# V2.net
KiCad netlist of a schematic drawn in EAGLE
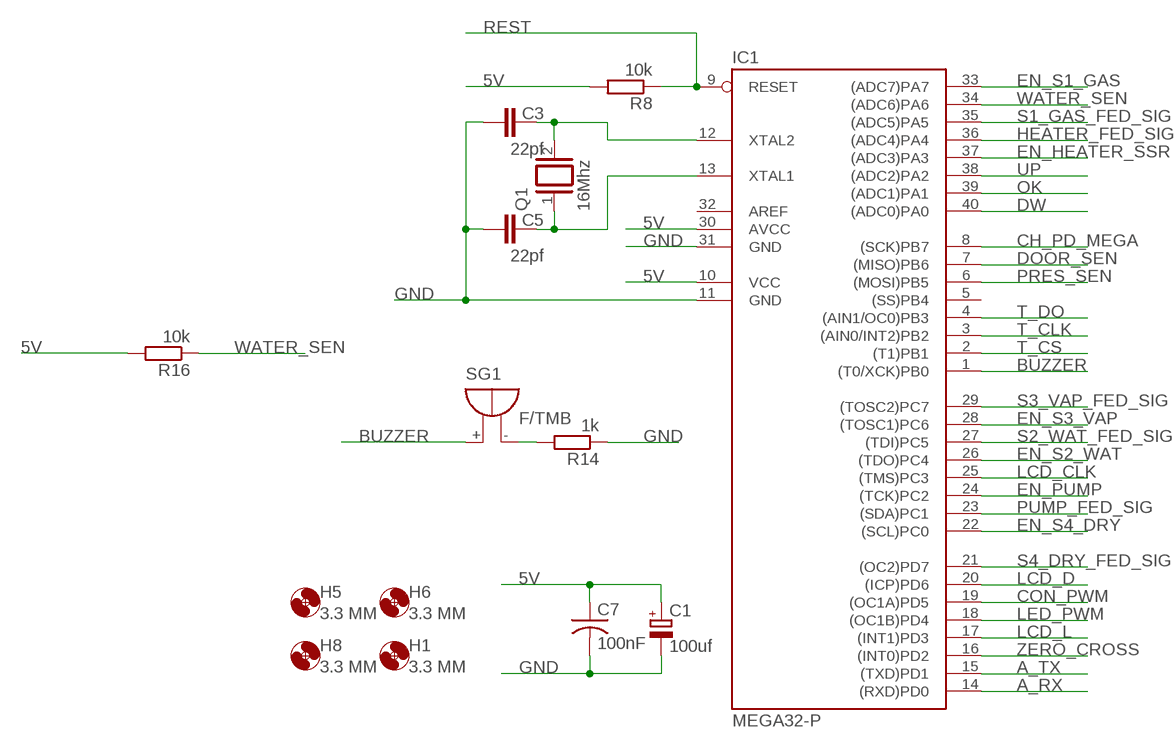
[diagram p0: schematic, sheet 1]
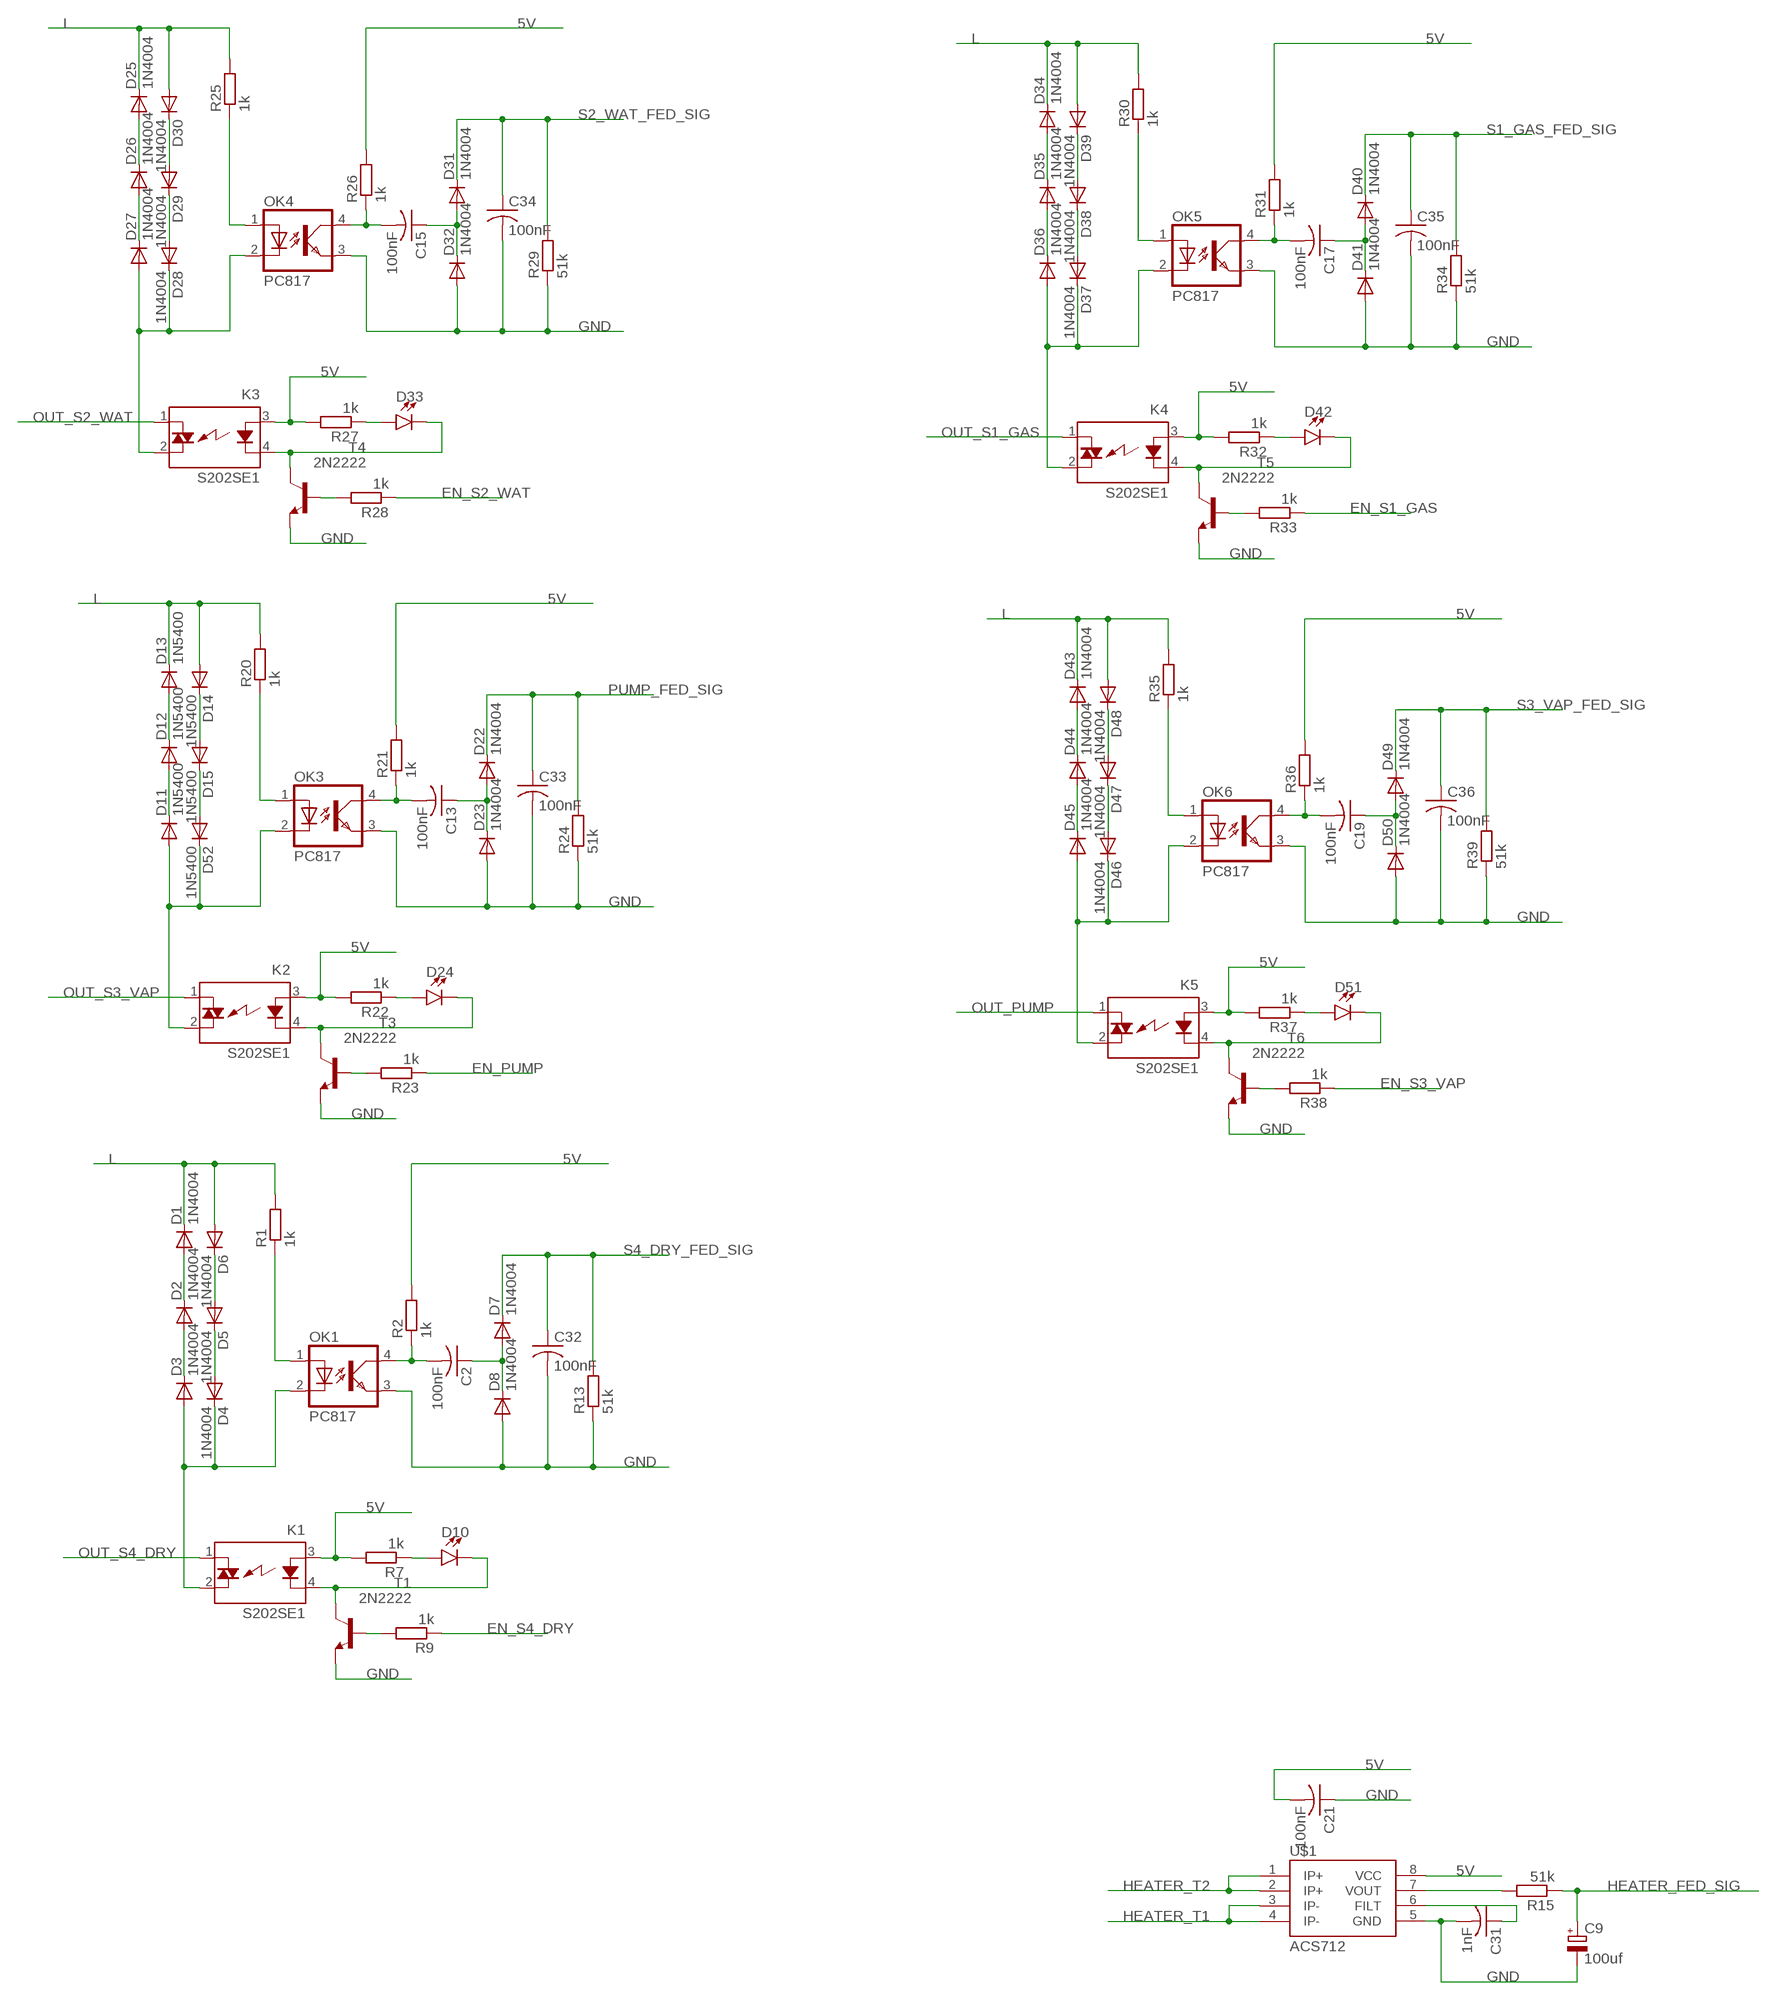
[diagram p1: schematic, sheet 2]
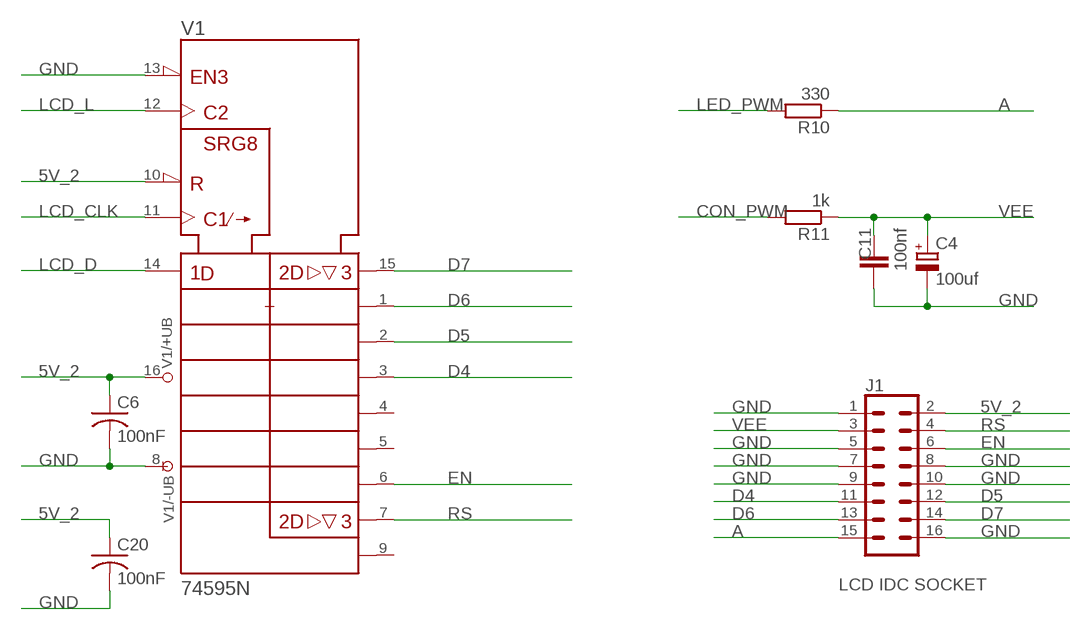
[diagram p2: schematic, sheet 3]
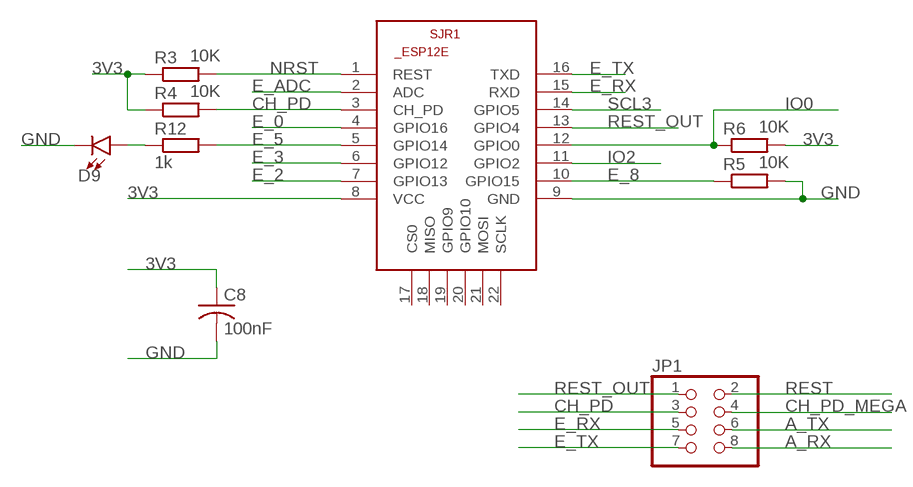
[diagram p3: schematic, sheet 4]
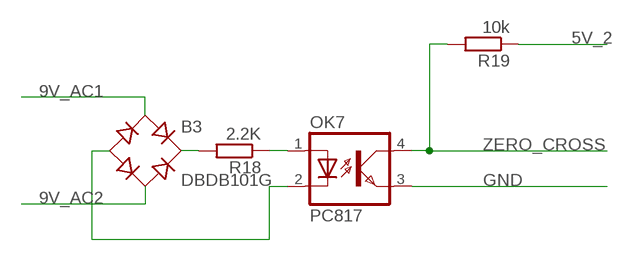
[diagram p4: schematic, sheet 5]
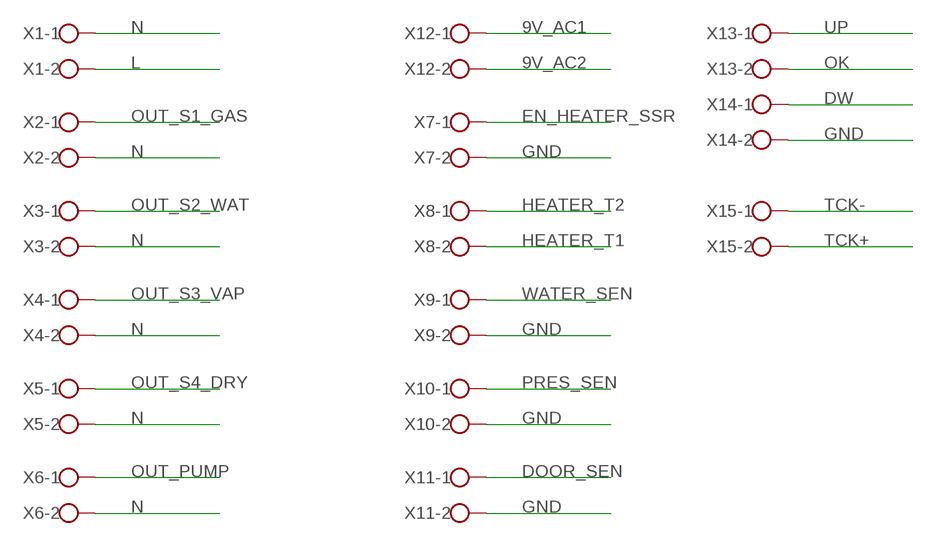
[diagram p5: schematic, sheet 6]
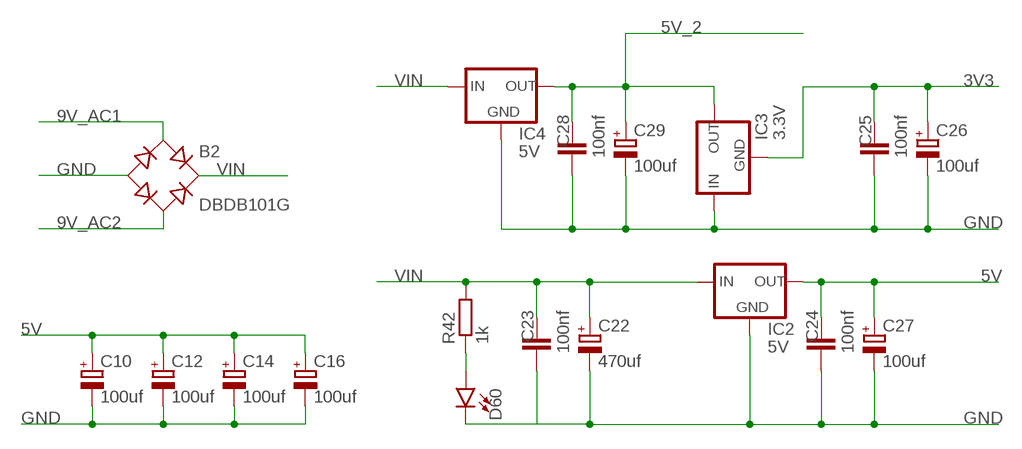
[diagram p6: schematic, sheet 7]
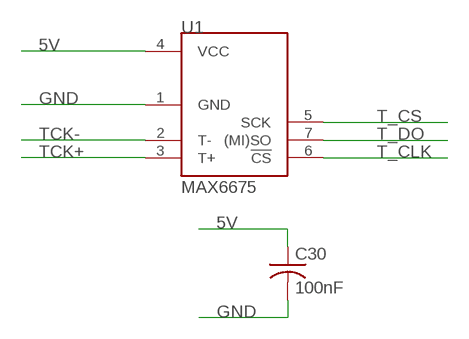
[diagram p7: schematic, sheet 8]

(export (version "E")
  (design (tool "Eeschema 10.0.6"))
  (components
    (comp (ref "C1")
      (value "100uf")
      (footprint "eagle-import:E3,5-8")
      (libsource (lib "eagle-import") (part "CPOL-EUE3.5-8"))
    )
    (comp (ref "C3")
      (value "22pf")
      (footprint "eagle-import:C050-030X075")
      (libsource (lib "eagle-import") (part "C-EU050-030X075"))
    )
    (comp (ref "C5")
      (value "22pf")
      (footprint "eagle-import:C050-030X075")
      (libsource (lib "eagle-import") (part "C-EU050-030X075"))
    )
    (comp (ref "C7")
      (value "100nF")
      (footprint "eagle-import:C050-035X075")
      (libsource (lib "eagle-import") (part "C-US050-035X075"))
    )
    (comp (ref "H1")
      (value "3.3 MM")
      (footprint "eagle-import:3,3")
      (libsource (lib "eagle-import") (part "MOUNT-HOLE3.3"))
    )
    (comp (ref "H5")
      (value "3.3 MM")
      (footprint "eagle-import:3,3")
      (libsource (lib "eagle-import") (part "MOUNT-HOLE3.3"))
    )
    (comp (ref "H6")
      (value "3.3 MM")
      (footprint "eagle-import:3,3")
      (libsource (lib "eagle-import") (part "MOUNT-HOLE3.3"))
    )
    (comp (ref "H8")
      (value "3.3 MM")
      (footprint "eagle-import:3,3")
      (libsource (lib "eagle-import") (part "MOUNT-HOLE3.3"))
    )
    (comp (ref "IC1")
      (value "MEGA32-P")
      (footprint "eagle-import:DIL40")
      (fields (field (name "MPN") "ATMEGA32-16PU"))
      (libsource (lib "eagle-import") (part "MEGA32-P"))
    )
    (comp (ref "Q1")
      (value "16Mhz")
      (footprint "eagle-import:QS")
      (libsource (lib "eagle-import") (part "XTAL/S"))
    )
    (comp (ref "R8")
      (value "10k")
      (footprint "eagle-import:0207_10")
      (libsource (lib "eagle-import") (part "R-EU_0207/10"))
    )
    (comp (ref "R14")
      (value "1k")
      (footprint "eagle-import:0207_10")
      (libsource (lib "eagle-import") (part "R-EU_0207/10"))
    )
    (comp (ref "R16")
      (value "10k")
      (footprint "eagle-import:0207_10")
      (libsource (lib "eagle-import") (part "R-EU_0207/10"))
    )
    (comp (ref "SG1")
      (value "F/TMB")
      (footprint "eagle-import:F_TMB")
      (libsource (lib "eagle-import") (part "F/TMB"))
    )
    (comp (ref "X1")
      (value "W237-102")
      (footprint "eagle-import:W237-102")
      (fields (field (name "MPN") "237-102"))
      (libsource (lib "eagle-import") (part "W237-102"))
    )
    (comp (ref "X2")
      (value "W237-102")
      (footprint "eagle-import:W237-102")
      (fields (field (name "MPN") "237-102"))
      (libsource (lib "eagle-import") (part "W237-102"))
    )
    (comp (ref "X3")
      (value "W237-102")
      (footprint "eagle-import:W237-102")
      (fields (field (name "MPN") "237-102"))
      (libsource (lib "eagle-import") (part "W237-102"))
    )
    (comp (ref "X4")
      (value "W237-102")
      (footprint "eagle-import:W237-102")
      (fields (field (name "MPN") "237-102"))
      (libsource (lib "eagle-import") (part "W237-102"))
    )
    (comp (ref "X5")
      (value "W237-102")
      (footprint "eagle-import:W237-102")
      (fields (field (name "MPN") "237-102"))
      (libsource (lib "eagle-import") (part "W237-102"))
    )
    (comp (ref "X6")
      (value "W237-102")
      (footprint "eagle-import:W237-102")
      (fields (field (name "MPN") "237-102"))
      (libsource (lib "eagle-import") (part "W237-102"))
    )
    (comp (ref "X7")
      (value "W237-102")
      (footprint "eagle-import:W237-102")
      (fields (field (name "MPN") "237-102"))
      (libsource (lib "eagle-import") (part "W237-102"))
    )
    (comp (ref "X8")
      (value "W237-102")
      (footprint "eagle-import:W237-102")
      (fields (field (name "MPN") "237-102"))
      (libsource (lib "eagle-import") (part "W237-102"))
    )
    (comp (ref "X9")
      (value "W237-102")
      (footprint "eagle-import:W237-102")
      (fields (field (name "MPN") "237-102"))
      (libsource (lib "eagle-import") (part "W237-102"))
    )
    (comp (ref "X10")
      (value "W237-102")
      (footprint "eagle-import:W237-102")
      (fields (field (name "MPN") "237-102"))
      (libsource (lib "eagle-import") (part "W237-102"))
    )
    (comp (ref "X11")
      (value "W237-102")
      (footprint "eagle-import:W237-102")
      (fields (field (name "MPN") "237-102"))
      (libsource (lib "eagle-import") (part "W237-102"))
    )
    (comp (ref "X12")
      (value "W237-102")
      (footprint "eagle-import:W237-102")
      (fields (field (name "MPN") "237-102"))
      (libsource (lib "eagle-import") (part "W237-102"))
    )
    (comp (ref "X13")
      (value "W237-102")
      (footprint "eagle-import:W237-102")
      (fields (field (name "MPN") "237-102"))
      (libsource (lib "eagle-import") (part "W237-102"))
    )
    (comp (ref "X14")
      (value "W237-102")
      (footprint "eagle-import:W237-102")
      (fields (field (name "MPN") "237-102"))
      (libsource (lib "eagle-import") (part "W237-102"))
    )
    (comp (ref "X15")
      (value "W237-102")
      (footprint "eagle-import:W237-102")
      (fields (field (name "MPN") "237-102"))
      (libsource (lib "eagle-import") (part "W237-102"))
    )
    (comp (ref "C4")
      (value "100uf")
      (footprint "eagle-import:E3,5-8")
      (libsource (lib "eagle-import") (part "CPOL-EUE3.5-8"))
    )
    (comp (ref "C6")
      (value "100nF")
      (footprint "eagle-import:C050-035X075")
      (libsource (lib "eagle-import") (part "C-US050-035X075"))
    )
    (comp (ref "C11")
      (value "100nf")
      (footprint "eagle-import:C050-030X075")
      (libsource (lib "eagle-import") (part "C-EU050-030X075"))
    )
    (comp (ref "C20")
      (value "100nF")
      (footprint "eagle-import:C050-035X075")
      (libsource (lib "eagle-import") (part "C-US050-035X075"))
    )
    (comp (ref "J1")
      (value "CONN_08X2")
      (footprint "eagle-import:2X8")
      (libsource (lib "eagle-import") (part "CONN_08X2"))
    )
    (comp (ref "R10")
      (value "330")
      (footprint "eagle-import:0207_10")
      (libsource (lib "eagle-import") (part "R-EU_0207/10"))
    )
    (comp (ref "R11")
      (value "1k")
      (footprint "eagle-import:0207_10")
      (libsource (lib "eagle-import") (part "R-EU_0207/10"))
    )
    (comp (ref "V1")
      (value "74595N")
      (footprint "eagle-import:DIL16")
      (libsource (lib "eagle-import") (part "74595N"))
    )
    (comp (ref "B2")
      (value "DBDB101G")
      (footprint "eagle-import:DB")
      (libsource (lib "eagle-import") (part "DB?GDB101"))
    )
    (comp (ref "C10")
      (value "100uf")
      (footprint "eagle-import:E3,5-8")
      (libsource (lib "eagle-import") (part "CPOL-EUE3.5-8"))
    )
    (comp (ref "C12")
      (value "100uf")
      (footprint "eagle-import:E3,5-8")
      (libsource (lib "eagle-import") (part "CPOL-EUE3.5-8"))
    )
    (comp (ref "C14")
      (value "100uf")
      (footprint "eagle-import:E3,5-8")
      (libsource (lib "eagle-import") (part "CPOL-EUE3.5-8"))
    )
    (comp (ref "C16")
      (value "100uf")
      (footprint "eagle-import:E3,5-8")
      (libsource (lib "eagle-import") (part "CPOL-EUE3.5-8"))
    )
    (comp (ref "C22")
      (value "470uf")
      (footprint "eagle-import:E3,5-8")
      (libsource (lib "eagle-import") (part "CPOL-EUE3.5-8"))
    )
    (comp (ref "C23")
      (value "100nf")
      (footprint "eagle-import:C050-030X075")
      (libsource (lib "eagle-import") (part "C-EU050-030X075"))
    )
    (comp (ref "C24")
      (value "100nf")
      (footprint "eagle-import:C050-030X075")
      (libsource (lib "eagle-import") (part "C-EU050-030X075"))
    )
    (comp (ref "C25")
      (value "100nf")
      (footprint "eagle-import:C050-030X075")
      (libsource (lib "eagle-import") (part "C-EU050-030X075"))
    )
    (comp (ref "C26")
      (value "100uf")
      (footprint "eagle-import:E3,5-8")
      (libsource (lib "eagle-import") (part "CPOL-EUE3.5-8"))
    )
    (comp (ref "C27")
      (value "100uf")
      (footprint "eagle-import:E3,5-8")
      (libsource (lib "eagle-import") (part "CPOL-EUE3.5-8"))
    )
    (comp (ref "C28")
      (value "100nf")
      (footprint "eagle-import:C050-030X075")
      (libsource (lib "eagle-import") (part "C-EU050-030X075"))
    )
    (comp (ref "C29")
      (value "100uf")
      (footprint "eagle-import:E3,5-8")
      (libsource (lib "eagle-import") (part "CPOL-EUE3.5-8"))
    )
    (comp (ref "D60")
      (value "LED5MM")
      (footprint "eagle-import:LED_5MM")
      (libsource (lib "eagle-import") (part "LED5MM"))
    )
    (comp (ref "IC2")
      (value "5V")
      (footprint "eagle-import:78XXL")
      (libsource (lib "eagle-import") (part "V_REG_78XXSIDE"))
    )
    (comp (ref "IC3")
      (value "3.3V")
      (footprint "eagle-import:78XXL")
      (libsource (lib "eagle-import") (part "V_REG_78XXSIDE"))
    )
    (comp (ref "IC4")
      (value "5V")
      (footprint "eagle-import:78XXL")
      (libsource (lib "eagle-import") (part "V_REG_78XXSIDE"))
    )
    (comp (ref "R42")
      (value "1k")
      (footprint "eagle-import:0207_10")
      (libsource (lib "eagle-import") (part "R-EU_0207/10"))
    )
    (comp (ref "C2")
      (value "100nF")
      (footprint "eagle-import:C050-035X075")
      (libsource (lib "eagle-import") (part "C-US050-035X075"))
    )
    (comp (ref "C9")
      (value "100uf")
      (footprint "eagle-import:E3,5-8")
      (libsource (lib "eagle-import") (part "CPOL-EUE3.5-8"))
    )
    (comp (ref "C13")
      (value "100nF")
      (footprint "eagle-import:C050-035X075")
      (libsource (lib "eagle-import") (part "C-US050-035X075"))
    )
    (comp (ref "C15")
      (value "100nF")
      (footprint "eagle-import:C050-035X075")
      (libsource (lib "eagle-import") (part "C-US050-035X075"))
    )
    (comp (ref "C17")
      (value "100nF")
      (footprint "eagle-import:C050-035X075")
      (libsource (lib "eagle-import") (part "C-US050-035X075"))
    )
    (comp (ref "C19")
      (value "100nF")
      (footprint "eagle-import:C050-035X075")
      (libsource (lib "eagle-import") (part "C-US050-035X075"))
    )
    (comp (ref "C21")
      (value "100nF")
      (footprint "eagle-import:C050-035X075")
      (libsource (lib "eagle-import") (part "C-US050-035X075"))
    )
    (comp (ref "C31")
      (value "1nF")
      (footprint "eagle-import:C050-035X075")
      (libsource (lib "eagle-import") (part "C-US050-035X075"))
    )
    (comp (ref "C32")
      (value "100nF")
      (footprint "eagle-import:C050-035X075")
      (libsource (lib "eagle-import") (part "C-US050-035X075"))
    )
    (comp (ref "C33")
      (value "100nF")
      (footprint "eagle-import:C050-035X075")
      (libsource (lib "eagle-import") (part "C-US050-035X075"))
    )
    (comp (ref "C34")
      (value "100nF")
      (footprint "eagle-import:C050-035X075")
      (libsource (lib "eagle-import") (part "C-US050-035X075"))
    )
    (comp (ref "C35")
      (value "100nF")
      (footprint "eagle-import:C050-035X075")
      (libsource (lib "eagle-import") (part "C-US050-035X075"))
    )
    (comp (ref "C36")
      (value "100nF")
      (footprint "eagle-import:C050-035X075")
      (libsource (lib "eagle-import") (part "C-US050-035X075"))
    )
    (comp (ref "D1")
      (value "1N4004")
      (footprint "eagle-import:DO41-10")
      (libsource (lib "eagle-import") (part "1N4004"))
    )
    (comp (ref "D2")
      (value "1N4004")
      (footprint "eagle-import:DO41-10")
      (libsource (lib "eagle-import") (part "1N4004"))
    )
    (comp (ref "D3")
      (value "1N4004")
      (footprint "eagle-import:DO41-10")
      (libsource (lib "eagle-import") (part "1N4004"))
    )
    (comp (ref "D4")
      (value "1N4004")
      (footprint "eagle-import:DO41-10")
      (libsource (lib "eagle-import") (part "1N4004"))
    )
    (comp (ref "D5")
      (value "1N4004")
      (footprint "eagle-import:DO41-10")
      (libsource (lib "eagle-import") (part "1N4004"))
    )
    (comp (ref "D6")
      (value "1N4004")
      (footprint "eagle-import:DO41-10")
      (libsource (lib "eagle-import") (part "1N4004"))
    )
    (comp (ref "D7")
      (value "1N4004")
      (footprint "eagle-import:DO41-10")
      (libsource (lib "eagle-import") (part "1N4004"))
    )
    (comp (ref "D8")
      (value "1N4004")
      (footprint "eagle-import:DO41-10")
      (libsource (lib "eagle-import") (part "1N4004"))
    )
    (comp (ref "D10")
      (value "LED5MM")
      (footprint "eagle-import:LED_5MM")
      (libsource (lib "eagle-import") (part "LED5MM"))
    )
    (comp (ref "D11")
      (value "1N5400")
      (footprint "eagle-import:DO201-15")
      (libsource (lib "eagle-import") (part "1N5400"))
    )
    (comp (ref "D12")
      (value "1N5400")
      (footprint "eagle-import:DO201-15")
      (libsource (lib "eagle-import") (part "1N5400"))
    )
    (comp (ref "D13")
      (value "1N5400")
      (footprint "eagle-import:DO201-15")
      (libsource (lib "eagle-import") (part "1N5400"))
    )
    (comp (ref "D14")
      (value "1N5400")
      (footprint "eagle-import:DO201-15")
      (libsource (lib "eagle-import") (part "1N5400"))
    )
    (comp (ref "D15")
      (value "1N5400")
      (footprint "eagle-import:DO201-15")
      (libsource (lib "eagle-import") (part "1N5400"))
    )
    (comp (ref "D22")
      (value "1N4004")
      (footprint "eagle-import:DO41-10")
      (libsource (lib "eagle-import") (part "1N4004"))
    )
    (comp (ref "D23")
      (value "1N4004")
      (footprint "eagle-import:DO41-10")
      (libsource (lib "eagle-import") (part "1N4004"))
    )
    (comp (ref "D24")
      (value "LED5MM")
      (footprint "eagle-import:LED_5MM")
      (libsource (lib "eagle-import") (part "LED5MM"))
    )
    (comp (ref "D25")
      (value "1N4004")
      (footprint "eagle-import:DO41-10")
      (libsource (lib "eagle-import") (part "1N4004"))
    )
    (comp (ref "D26")
      (value "1N4004")
      (footprint "eagle-import:DO41-10")
      (libsource (lib "eagle-import") (part "1N4004"))
    )
    (comp (ref "D27")
      (value "1N4004")
      (footprint "eagle-import:DO41-10")
      (libsource (lib "eagle-import") (part "1N4004"))
    )
    (comp (ref "D28")
      (value "1N4004")
      (footprint "eagle-import:DO41-10")
      (libsource (lib "eagle-import") (part "1N4004"))
    )
    (comp (ref "D29")
      (value "1N4004")
      (footprint "eagle-import:DO41-10")
      (libsource (lib "eagle-import") (part "1N4004"))
    )
    (comp (ref "D30")
      (value "1N4004")
      (footprint "eagle-import:DO41-10")
      (libsource (lib "eagle-import") (part "1N4004"))
    )
    (comp (ref "D31")
      (value "1N4004")
      (footprint "eagle-import:DO41-10")
      (libsource (lib "eagle-import") (part "1N4004"))
    )
    (comp (ref "D32")
      (value "1N4004")
      (footprint "eagle-import:DO41-10")
      (libsource (lib "eagle-import") (part "1N4004"))
    )
    (comp (ref "D33")
      (value "LED5MM")
      (footprint "eagle-import:LED_5MM")
      (libsource (lib "eagle-import") (part "LED5MM"))
    )
    (comp (ref "D34")
      (value "1N4004")
      (footprint "eagle-import:DO41-10")
      (libsource (lib "eagle-import") (part "1N4004"))
    )
    (comp (ref "D35")
      (value "1N4004")
      (footprint "eagle-import:DO41-10")
      (libsource (lib "eagle-import") (part "1N4004"))
    )
    (comp (ref "D36")
      (value "1N4004")
      (footprint "eagle-import:DO41-10")
      (libsource (lib "eagle-import") (part "1N4004"))
    )
    (comp (ref "D37")
      (value "1N4004")
      (footprint "eagle-import:DO41-10")
      (libsource (lib "eagle-import") (part "1N4004"))
    )
    (comp (ref "D38")
      (value "1N4004")
      (footprint "eagle-import:DO41-10")
      (libsource (lib "eagle-import") (part "1N4004"))
    )
    (comp (ref "D39")
      (value "1N4004")
      (footprint "eagle-import:DO41-10")
      (libsource (lib "eagle-import") (part "1N4004"))
    )
    (comp (ref "D40")
      (value "1N4004")
      (footprint "eagle-import:DO41-10")
      (libsource (lib "eagle-import") (part "1N4004"))
    )
    (comp (ref "D41")
      (value "1N4004")
      (footprint "eagle-import:DO41-10")
      (libsource (lib "eagle-import") (part "1N4004"))
    )
    (comp (ref "D42")
      (value "LED5MM")
      (footprint "eagle-import:LED_5MM")
      (libsource (lib "eagle-import") (part "LED5MM"))
    )
    (comp (ref "D43")
      (value "1N4004")
      (footprint "eagle-import:DO41-10")
      (libsource (lib "eagle-import") (part "1N4004"))
    )
    (comp (ref "D44")
      (value "1N4004")
      (footprint "eagle-import:DO41-10")
      (libsource (lib "eagle-import") (part "1N4004"))
    )
    (comp (ref "D45")
      (value "1N4004")
      (footprint "eagle-import:DO41-10")
      (libsource (lib "eagle-import") (part "1N4004"))
    )
    (comp (ref "D46")
      (value "1N4004")
      (footprint "eagle-import:DO41-10")
      (libsource (lib "eagle-import") (part "1N4004"))
    )
    (comp (ref "D47")
      (value "1N4004")
      (footprint "eagle-import:DO41-10")
      (libsource (lib "eagle-import") (part "1N4004"))
    )
    (comp (ref "D48")
      (value "1N4004")
      (footprint "eagle-import:DO41-10")
      (libsource (lib "eagle-import") (part "1N4004"))
    )
    (comp (ref "D49")
      (value "1N4004")
      (footprint "eagle-import:DO41-10")
      (libsource (lib "eagle-import") (part "1N4004"))
    )
    (comp (ref "D50")
      (value "1N4004")
      (footprint "eagle-import:DO41-10")
      (libsource (lib "eagle-import") (part "1N4004"))
    )
    (comp (ref "D51")
      (value "LED5MM")
      (footprint "eagle-import:LED_5MM")
      (libsource (lib "eagle-import") (part "LED5MM"))
    )
    (comp (ref "D52")
      (value "1N5400")
      (footprint "eagle-import:DO201-15")
      (libsource (lib "eagle-import") (part "1N5400"))
    )
    (comp (ref "K1")
      (value "S202SE1")
      (footprint "eagle-import:S2XXEX")
      (libsource (lib "eagle-import") (part "S202SE1"))
    )
    (comp (ref "K2")
      (value "S202SE1")
      (footprint "eagle-import:S2XXEX")
      (libsource (lib "eagle-import") (part "S202SE1"))
    )
    (comp (ref "K3")
      (value "S202SE1")
      (footprint "eagle-import:S2XXEX")
      (libsource (lib "eagle-import") (part "S202SE1"))
    )
    (comp (ref "K4")
      (value "S202SE1")
      (footprint "eagle-import:S2XXEX")
      (libsource (lib "eagle-import") (part "S202SE1"))
    )
    (comp (ref "K5")
      (value "S202SE1")
      (footprint "eagle-import:S2XXEX")
      (libsource (lib "eagle-import") (part "S202SE1"))
    )
    (comp (ref "OK1")
      (value "PC817")
      (footprint "eagle-import:DIL04")
      (libsource (lib "eagle-import") (part "PC817"))
    )
    (comp (ref "OK3")
      (value "PC817")
      (footprint "eagle-import:DIL04")
      (libsource (lib "eagle-import") (part "PC817"))
    )
    (comp (ref "OK4")
      (value "PC817")
      (footprint "eagle-import:DIL04")
      (libsource (lib "eagle-import") (part "PC817"))
    )
    (comp (ref "OK5")
      (value "PC817")
      (footprint "eagle-import:DIL04")
      (libsource (lib "eagle-import") (part "PC817"))
    )
    (comp (ref "OK6")
      (value "PC817")
      (footprint "eagle-import:DIL04")
      (libsource (lib "eagle-import") (part "PC817"))
    )
    (comp (ref "R1")
      (value "1k")
      (footprint "eagle-import:0207_10")
      (libsource (lib "eagle-import") (part "R-EU_0207/10"))
    )
    (comp (ref "R2")
      (value "1k")
      (footprint "eagle-import:0207_10")
      (libsource (lib "eagle-import") (part "R-EU_0207/10"))
    )
    (comp (ref "R7")
      (value "1k")
      (footprint "eagle-import:0207_10")
      (libsource (lib "eagle-import") (part "R-EU_0207/10"))
    )
    (comp (ref "R9")
      (value "1k")
      (footprint "eagle-import:0207_10")
      (libsource (lib "eagle-import") (part "R-EU_0207/10"))
    )
    (comp (ref "R13")
      (value "51k")
      (footprint "eagle-import:0207_10")
      (libsource (lib "eagle-import") (part "R-EU_0207/10"))
    )
    (comp (ref "R15")
      (value "51k")
      (footprint "eagle-import:0207_10")
      (libsource (lib "eagle-import") (part "R-EU_0207/10"))
    )
    (comp (ref "R20")
      (value "1k")
      (footprint "eagle-import:0207_10")
      (libsource (lib "eagle-import") (part "R-EU_0207/10"))
    )
    (comp (ref "R21")
      (value "1k")
      (footprint "eagle-import:0207_10")
      (libsource (lib "eagle-import") (part "R-EU_0207/10"))
    )
    (comp (ref "R22")
      (value "1k")
      (footprint "eagle-import:0207_10")
      (libsource (lib "eagle-import") (part "R-EU_0207/10"))
    )
    (comp (ref "R23")
      (value "1k")
      (footprint "eagle-import:0207_10")
      (libsource (lib "eagle-import") (part "R-EU_0207/10"))
    )
    (comp (ref "R24")
      (value "51k")
      (footprint "eagle-import:0207_10")
      (libsource (lib "eagle-import") (part "R-EU_0207/10"))
    )
    (comp (ref "R25")
      (value "1k")
      (footprint "eagle-import:0207_10")
      (libsource (lib "eagle-import") (part "R-EU_0207/10"))
    )
    (comp (ref "R26")
      (value "1k")
      (footprint "eagle-import:0207_10")
      (libsource (lib "eagle-import") (part "R-EU_0207/10"))
    )
    (comp (ref "R27")
      (value "1k")
      (footprint "eagle-import:0207_10")
      (libsource (lib "eagle-import") (part "R-EU_0207/10"))
    )
    (comp (ref "R28")
      (value "1k")
      (footprint "eagle-import:0207_10")
      (libsource (lib "eagle-import") (part "R-EU_0207/10"))
    )
    (comp (ref "R29")
      (value "51k")
      (footprint "eagle-import:0207_10")
      (libsource (lib "eagle-import") (part "R-EU_0207/10"))
    )
    (comp (ref "R30")
      (value "1k")
      (footprint "eagle-import:0207_10")
      (libsource (lib "eagle-import") (part "R-EU_0207/10"))
    )
    (comp (ref "R31")
      (value "1k")
      (footprint "eagle-import:0207_10")
      (libsource (lib "eagle-import") (part "R-EU_0207/10"))
    )
    (comp (ref "R32")
      (value "1k")
      (footprint "eagle-import:0207_10")
      (libsource (lib "eagle-import") (part "R-EU_0207/10"))
    )
    (comp (ref "R33")
      (value "1k")
      (footprint "eagle-import:0207_10")
      (libsource (lib "eagle-import") (part "R-EU_0207/10"))
    )
    (comp (ref "R34")
      (value "51k")
      (footprint "eagle-import:0207_10")
      (libsource (lib "eagle-import") (part "R-EU_0207/10"))
    )
    (comp (ref "R35")
      (value "1k")
      (footprint "eagle-import:0207_10")
      (libsource (lib "eagle-import") (part "R-EU_0207/10"))
    )
    (comp (ref "R36")
      (value "1k")
      (footprint "eagle-import:0207_10")
      (libsource (lib "eagle-import") (part "R-EU_0207/10"))
    )
    (comp (ref "R37")
      (value "1k")
      (footprint "eagle-import:0207_10")
      (libsource (lib "eagle-import") (part "R-EU_0207/10"))
    )
    (comp (ref "R38")
      (value "1k")
      (footprint "eagle-import:0207_10")
      (libsource (lib "eagle-import") (part "R-EU_0207/10"))
    )
    (comp (ref "R39")
      (value "51k")
      (footprint "eagle-import:0207_10")
      (libsource (lib "eagle-import") (part "R-EU_0207/10"))
    )
    (comp (ref "T1")
      (value "2N2222")
      (footprint "eagle-import:TO92-EBC-OVAL")
      (libsource (lib "eagle-import") (part "2N2222"))
    )
    (comp (ref "T3")
      (value "2N2222")
      (footprint "eagle-import:TO92-EBC-OVAL")
      (libsource (lib "eagle-import") (part "2N2222"))
    )
    (comp (ref "T4")
      (value "2N2222")
      (footprint "eagle-import:TO92-EBC-OVAL")
      (libsource (lib "eagle-import") (part "2N2222"))
    )
    (comp (ref "T5")
      (value "2N2222")
      (footprint "eagle-import:TO92-EBC-OVAL")
      (libsource (lib "eagle-import") (part "2N2222"))
    )
    (comp (ref "T6")
      (value "2N2222")
      (footprint "eagle-import:TO92-EBC-OVAL")
      (libsource (lib "eagle-import") (part "2N2222"))
    )
    (comp (ref "U$1")
      (value "ACS712")
      (footprint "eagle-import:SO08")
      (libsource (lib "eagle-import") (part "ACS712"))
    )
    (comp (ref "C8")
      (value "100nF")
      (footprint "eagle-import:C050-035X075")
      (libsource (lib "eagle-import") (part "C-US050-035X075"))
    )
    (comp (ref "D9")
      (value "LED5MM")
      (footprint "eagle-import:LED_5MM")
      (libsource (lib "eagle-import") (part "LED5MM"))
    )
    (comp (ref "JP1")
      (value "PINHD-2X4")
      (footprint "eagle-import:2X04")
      (libsource (lib "eagle-import") (part "PINHD-2X4"))
    )
    (comp (ref "R3")
      (value "10K")
      (footprint "eagle-import:0207_10")
      (libsource (lib "eagle-import") (part "rcl_334_R-EU_0207/10"))
    )
    (comp (ref "R4")
      (value "10K")
      (footprint "eagle-import:0207_10")
      (libsource (lib "eagle-import") (part "rcl_334_R-EU_0207/10"))
    )
    (comp (ref "R5")
      (value "10K")
      (footprint "eagle-import:0207_10")
      (libsource (lib "eagle-import") (part "rcl_334_R-EU_0207/10"))
    )
    (comp (ref "R6")
      (value "10K")
      (footprint "eagle-import:0207_10")
      (libsource (lib "eagle-import") (part "rcl_334_R-EU_0207/10"))
    )
    (comp (ref "R12")
      (value "1k")
      (footprint "eagle-import:0207_10")
      (libsource (lib "eagle-import") (part "R-EU_0207/10"))
    )
    (comp (ref "SJR1")
      (value "ESP8266-12EESP12E")
      (footprint "eagle-import:ESP8266-ESP12E")
      (libsource (lib "eagle-import") (part "ESP8266-12EESP12E"))
    )
    (comp (ref "C30")
      (value "100nF")
      (footprint "eagle-import:C050-035X075")
      (libsource (lib "eagle-import") (part "C-US050-035X075"))
    )
    (comp (ref "U1")
      (value "MAX6675")
      (footprint "eagle-import:SOIC8")
      (libsource (lib "eagle-import") (part "MAX6675"))
    )
    (comp (ref "B3")
      (value "DBDB101G")
      (footprint "eagle-import:DB")
      (libsource (lib "eagle-import") (part "DB?GDB101"))
    )
    (comp (ref "OK7")
      (value "PC817")
      (footprint "eagle-import:DIL04")
      (libsource (lib "eagle-import") (part "PC817"))
    )
    (comp (ref "R18")
      (value "2.2K")
      (footprint "eagle-import:0207_10")
      (libsource (lib "eagle-import") (part "R-EU_0207/10"))
    )
    (comp (ref "R19")
      (value "10k")
      (footprint "eagle-import:0207_10")
      (libsource (lib "eagle-import") (part "R-EU_0207/10"))
    )
  )
  (nets
    (net (code "1") (name "3V3") (class "Default")
      (node (ref "C25") (pin "2") (pinfunction "2_2") (pintype "passive"))
      (node (ref "C26") (pin "+") (pinfunction "+_+") (pintype "passive"))
      (node (ref "C8") (pin "1") (pinfunction "1_1") (pintype "passive"))
      (node (ref "IC3") (pin "GND") (pinfunction "GND_GND") (pintype "input"))
      (node (ref "R3") (pin "1") (pinfunction "1_1") (pintype "passive"))
      (node (ref "R4") (pin "1") (pinfunction "1_1") (pintype "passive"))
      (node (ref "R6") (pin "2") (pinfunction "2_2") (pintype "passive"))
      (node (ref "SJR1") (pin "8") (pinfunction "VCC_8") (pintype "bidirectional"))
    )
    (net (code "2") (name "5V") (class "Default")
      (node (ref "C1") (pin "+") (pinfunction "+_+") (pintype "passive"))
      (node (ref "C10") (pin "+") (pinfunction "+_+") (pintype "passive"))
      (node (ref "C12") (pin "+") (pinfunction "+_+") (pintype "passive"))
      (node (ref "C14") (pin "+") (pinfunction "+_+") (pintype "passive"))
      (node (ref "C16") (pin "+") (pinfunction "+_+") (pintype "passive"))
      (node (ref "C21") (pin "2") (pinfunction "2_2") (pintype "passive"))
      (node (ref "C24") (pin "2") (pinfunction "2_2") (pintype "passive"))
      (node (ref "C27") (pin "+") (pinfunction "+_+") (pintype "passive"))
      (node (ref "C30") (pin "1") (pinfunction "1_1") (pintype "passive"))
      (node (ref "C7") (pin "1") (pinfunction "1_1") (pintype "passive"))
      (node (ref "IC1") (pin "10") (pinfunction "VCC_10") (pintype "power_in"))
      (node (ref "IC1") (pin "30") (pinfunction "AVCC_30") (pintype "power_in"))
      (node (ref "IC2") (pin "OUT") (pinfunction "OUT_OUT") (pintype "output"))
      (node (ref "K1") (pin "3") (pinfunction "A_3") (pintype "passive"))
      (node (ref "K2") (pin "3") (pinfunction "A_3") (pintype "passive"))
      (node (ref "K3") (pin "3") (pinfunction "A_3") (pintype "passive"))
      (node (ref "K4") (pin "3") (pinfunction "A_3") (pintype "passive"))
      (node (ref "K5") (pin "3") (pinfunction "A_3") (pintype "passive"))
      (node (ref "R16") (pin "2") (pinfunction "2_2") (pintype "passive"))
      (node (ref "R2") (pin "2") (pinfunction "2_2") (pintype "passive"))
      (node (ref "R21") (pin "2") (pinfunction "2_2") (pintype "passive"))
      (node (ref "R22") (pin "2") (pinfunction "2_2") (pintype "passive"))
      (node (ref "R26") (pin "2") (pinfunction "2_2") (pintype "passive"))
      (node (ref "R27") (pin "2") (pinfunction "2_2") (pintype "passive"))
      (node (ref "R31") (pin "2") (pinfunction "2_2") (pintype "passive"))
      (node (ref "R32") (pin "2") (pinfunction "2_2") (pintype "passive"))
      (node (ref "R36") (pin "2") (pinfunction "2_2") (pintype "passive"))
      (node (ref "R37") (pin "2") (pinfunction "2_2") (pintype "passive"))
      (node (ref "R7") (pin "2") (pinfunction "2_2") (pintype "passive"))
      (node (ref "R8") (pin "2") (pinfunction "2_2") (pintype "passive"))
      (node (ref "U$1") (pin "8") (pinfunction "VCC_8") (pintype "bidirectional"))
      (node (ref "U1") (pin "4") (pinfunction "VCC_4") (pintype "bidirectional"))
    )
    (net (code "3") (name "5V_2") (class "Default")
      (node (ref "C20") (pin "1") (pinfunction "1_1") (pintype "passive"))
      (node (ref "C28") (pin "2") (pinfunction "2_2") (pintype "passive"))
      (node (ref "C29") (pin "+") (pinfunction "+_+") (pintype "passive"))
      (node (ref "C6") (pin "1") (pinfunction "1_1") (pintype "passive"))
      (node (ref "IC3") (pin "OUT") (pinfunction "OUT_OUT") (pintype "output"))
      (node (ref "IC4") (pin "OUT") (pinfunction "OUT_OUT") (pintype "output"))
      (node (ref "J1") (pin "2") (pinfunction "2_2") (pintype "passive"))
      (node (ref "R19") (pin "1") (pinfunction "1_1") (pintype "passive"))
      (node (ref "V1") (pin "10") (pinfunction "~{SRCLR}_10") (pintype "input"))
      (node (ref "V1") (pin "16") (pinfunction "+UB_16") (pintype "power_in"))
    )
    (net (code "4") (name "9V_AC1") (class "Default")
      (node (ref "B2") (pin "AC1") (pinfunction "AC1_AC1") (pintype "passive"))
      (node (ref "B3") (pin "AC1") (pinfunction "AC1_AC1") (pintype "passive"))
      (node (ref "X12") (pin "1") (pinfunction "KL_1") (pintype "passive"))
    )
    (net (code "5") (name "9V_AC2") (class "Default")
      (node (ref "B2") (pin "AC2") (pinfunction "AC2_AC2") (pintype "passive"))
      (node (ref "B3") (pin "AC2") (pinfunction "AC2_AC2") (pintype "passive"))
      (node (ref "X12") (pin "2") (pinfunction "KL_2") (pintype "passive"))
    )
    (net (code "6") (name "A") (class "Default")
      (node (ref "J1") (pin "15") (pinfunction "15_15") (pintype "passive"))
      (node (ref "R10") (pin "1") (pinfunction "1_1") (pintype "passive"))
    )
    (net (code "7") (name "A_RX") (class "Default")
      (node (ref "IC1") (pin "14") (pinfunction "(RXD)PD0_14") (pintype "bidirectional"))
      (node (ref "JP1") (pin "8") (pinfunction "8_8") (pintype "passive"))
    )
    (net (code "8") (name "A_TX") (class "Default")
      (node (ref "IC1") (pin "15") (pinfunction "(TXD)PD1_15") (pintype "bidirectional"))
      (node (ref "JP1") (pin "6") (pinfunction "6_6") (pintype "passive"))
    )
    (net (code "9") (name "BUZZER") (class "Default")
      (node (ref "IC1") (pin "1") (pinfunction "(T0/XCK)PB0_1") (pintype "bidirectional"))
      (node (ref "SG1") (pin "+") (pinfunction "+_+") (pintype "passive"))
    )
    (net (code "10") (name "CH_PD") (class "Default")
      (node (ref "JP1") (pin "3") (pinfunction "3_3") (pintype "passive"))
      (node (ref "R4") (pin "2") (pinfunction "2_2") (pintype "passive"))
      (node (ref "SJR1") (pin "3") (pinfunction "CH_PD_3") (pintype "bidirectional"))
    )
    (net (code "11") (name "CH_PD_MEGA") (class "Default")
      (node (ref "IC1") (pin "8") (pinfunction "(SCK)PB7_8") (pintype "bidirectional"))
      (node (ref "JP1") (pin "4") (pinfunction "4_4") (pintype "passive"))
    )
    (net (code "12") (name "CON_PWM") (class "Default")
      (node (ref "IC1") (pin "19") (pinfunction "(OC1A)PD5_19") (pintype "bidirectional"))
      (node (ref "R11") (pin "2") (pinfunction "2_2") (pintype "passive"))
    )
    (net (code "13") (name "D4") (class "Default")
      (node (ref "J1") (pin "11") (pinfunction "11_11") (pintype "passive"))
      (node (ref "V1") (pin "3") (pinfunction "QD_3") (pintype "tri_state"))
    )
    (net (code "14") (name "D5") (class "Default")
      (node (ref "J1") (pin "12") (pinfunction "12_12") (pintype "passive"))
      (node (ref "V1") (pin "2") (pinfunction "QC_2") (pintype "tri_state"))
    )
    (net (code "15") (name "D6") (class "Default")
      (node (ref "J1") (pin "13") (pinfunction "13_13") (pintype "passive"))
      (node (ref "V1") (pin "1") (pinfunction "QB_1") (pintype "tri_state"))
    )
    (net (code "16") (name "D7") (class "Default")
      (node (ref "J1") (pin "14") (pinfunction "14_14") (pintype "passive"))
      (node (ref "V1") (pin "15") (pinfunction "QA_15") (pintype "tri_state"))
    )
    (net (code "17") (name "DOOR_SEN") (class "Default")
      (node (ref "IC1") (pin "7") (pinfunction "(MISO)PB6_7") (pintype "bidirectional"))
      (node (ref "X11") (pin "1") (pinfunction "KL_1") (pintype "passive"))
    )
    (net (code "18") (name "DW") (class "Default")
      (node (ref "IC1") (pin "40") (pinfunction "(ADC0)PA0_40") (pintype "bidirectional"))
      (node (ref "X14") (pin "1") (pinfunction "KL_1") (pintype "passive"))
    )
    (net (code "19") (name "EN") (class "Default")
      (node (ref "J1") (pin "6") (pinfunction "6_6") (pintype "passive"))
      (node (ref "V1") (pin "6") (pinfunction "QG_6") (pintype "tri_state"))
    )
    (net (code "20") (name "EN_HEATER_SSR") (class "Default")
      (node (ref "IC1") (pin "37") (pinfunction "(ADC3)PA3_37") (pintype "bidirectional"))
      (node (ref "X7") (pin "1") (pinfunction "KL_1") (pintype "passive"))
    )
    (net (code "21") (name "EN_PUMP") (class "Default")
      (node (ref "IC1") (pin "24") (pinfunction "(TCK)PC2_24") (pintype "bidirectional"))
      (node (ref "R23") (pin "1") (pinfunction "1_1") (pintype "passive"))
    )
    (net (code "22") (name "EN_S1_GAS") (class "Default")
      (node (ref "IC1") (pin "33") (pinfunction "(ADC7)PA7_33") (pintype "bidirectional"))
      (node (ref "R33") (pin "1") (pinfunction "1_1") (pintype "passive"))
    )
    (net (code "23") (name "EN_S2_WAT") (class "Default")
      (node (ref "IC1") (pin "26") (pinfunction "(TDO)PC4_26") (pintype "bidirectional"))
      (node (ref "R28") (pin "1") (pinfunction "1_1") (pintype "passive"))
    )
    (net (code "24") (name "EN_S3_VAP") (class "Default")
      (node (ref "IC1") (pin "28") (pinfunction "(TOSC1)PC6_28") (pintype "bidirectional"))
      (node (ref "R38") (pin "1") (pinfunction "1_1") (pintype "passive"))
    )
    (net (code "25") (name "EN_S4_DRY") (class "Default")
      (node (ref "IC1") (pin "22") (pinfunction "(SCL)PC0_22") (pintype "bidirectional"))
      (node (ref "R9") (pin "1") (pinfunction "1_1") (pintype "passive"))
    )
    (net (code "26") (name "E_0") (class "Default")
      (node (ref "SJR1") (pin "4") (pinfunction "GPIO16_4") (pintype "bidirectional"))
    )
    (net (code "27") (name "E_2") (class "Default")
      (node (ref "SJR1") (pin "7") (pinfunction "GPIO13_7") (pintype "bidirectional"))
    )
    (net (code "28") (name "E_3") (class "Default")
      (node (ref "SJR1") (pin "6") (pinfunction "GPIO12_6") (pintype "bidirectional"))
    )
    (net (code "29") (name "E_5") (class "Default")
      (node (ref "R12") (pin "2") (pinfunction "2_2") (pintype "passive"))
      (node (ref "SJR1") (pin "5") (pinfunction "GPIO14_5") (pintype "bidirectional"))
    )
    (net (code "30") (name "E_8") (class "Default")
      (node (ref "R5") (pin "1") (pinfunction "1_1") (pintype "passive"))
      (node (ref "SJR1") (pin "10") (pinfunction "GPIO15_10") (pintype "bidirectional"))
    )
    (net (code "31") (name "E_ADC") (class "Default")
      (node (ref "SJR1") (pin "2") (pinfunction "ADC_2") (pintype "bidirectional"))
    )
    (net (code "32") (name "E_RX") (class "Default")
      (node (ref "JP1") (pin "5") (pinfunction "5_5") (pintype "passive"))
      (node (ref "SJR1") (pin "15") (pinfunction "RXD_15") (pintype "bidirectional"))
    )
    (net (code "33") (name "E_TX") (class "Default")
      (node (ref "JP1") (pin "7") (pinfunction "7_7") (pintype "passive"))
      (node (ref "SJR1") (pin "16") (pinfunction "TXD_16") (pintype "bidirectional"))
    )
    (net (code "34") (name "GND") (class "Default")
      (node (ref "B2") (pin "-") (pinfunction "-_-") (pintype "passive"))
      (node (ref "C1") (pin "-") (pinfunction "-_-") (pintype "passive"))
      (node (ref "C10") (pin "-") (pinfunction "-_-") (pintype "passive"))
      (node (ref "C11") (pin "1") (pinfunction "1_1") (pintype "passive"))
      (node (ref "C12") (pin "-") (pinfunction "-_-") (pintype "passive"))
      (node (ref "C14") (pin "-") (pinfunction "-_-") (pintype "passive"))
      (node (ref "C16") (pin "-") (pinfunction "-_-") (pintype "passive"))
      (node (ref "C20") (pin "2") (pinfunction "2_2") (pintype "passive"))
      (node (ref "C21") (pin "1") (pinfunction "1_1") (pintype "passive"))
      (node (ref "C22") (pin "-") (pinfunction "-_-") (pintype "passive"))
      (node (ref "C23") (pin "1") (pinfunction "1_1") (pintype "passive"))
      (node (ref "C24") (pin "1") (pinfunction "1_1") (pintype "passive"))
      (node (ref "C25") (pin "1") (pinfunction "1_1") (pintype "passive"))
      (node (ref "C26") (pin "-") (pinfunction "-_-") (pintype "passive"))
      (node (ref "C27") (pin "-") (pinfunction "-_-") (pintype "passive"))
      (node (ref "C28") (pin "1") (pinfunction "1_1") (pintype "passive"))
      (node (ref "C29") (pin "-") (pinfunction "-_-") (pintype "passive"))
      (node (ref "C3") (pin "1") (pinfunction "1_1") (pintype "passive"))
      (node (ref "C30") (pin "2") (pinfunction "2_2") (pintype "passive"))
      (node (ref "C31") (pin "2") (pinfunction "2_2") (pintype "passive"))
      (node (ref "C32") (pin "2") (pinfunction "2_2") (pintype "passive"))
      (node (ref "C33") (pin "2") (pinfunction "2_2") (pintype "passive"))
      (node (ref "C34") (pin "2") (pinfunction "2_2") (pintype "passive"))
      (node (ref "C35") (pin "2") (pinfunction "2_2") (pintype "passive"))
      (node (ref "C36") (pin "2") (pinfunction "2_2") (pintype "passive"))
      (node (ref "C4") (pin "-") (pinfunction "-_-") (pintype "passive"))
      (node (ref "C5") (pin "1") (pinfunction "1_1") (pintype "passive"))
      (node (ref "C6") (pin "2") (pinfunction "2_2") (pintype "passive"))
      (node (ref "C7") (pin "2") (pinfunction "2_2") (pintype "passive"))
      (node (ref "C8") (pin "2") (pinfunction "2_2") (pintype "passive"))
      (node (ref "C9") (pin "-") (pinfunction "-_-") (pintype "passive"))
      (node (ref "D23") (pin "A") (pinfunction "A_A") (pintype "passive"))
      (node (ref "D32") (pin "A") (pinfunction "A_A") (pintype "passive"))
      (node (ref "D41") (pin "A") (pinfunction "A_A") (pintype "passive"))
      (node (ref "D50") (pin "A") (pinfunction "A_A") (pintype "passive"))
      (node (ref "D60") (pin "K") (pinfunction "C_K") (pintype "passive"))
      (node (ref "D8") (pin "A") (pinfunction "A_A") (pintype "passive"))
      (node (ref "D9") (pin "K") (pinfunction "C_K") (pintype "passive"))
      (node (ref "IC1") (pin "11") (pinfunction "GND_11") (pintype "power_in"))
      (node (ref "IC1") (pin "31") (pinfunction "GND_31") (pintype "power_in"))
      (node (ref "IC2") (pin "GND") (pinfunction "GND_GND") (pintype "input"))
      (node (ref "IC3") (pin "IN") (pinfunction "IN_IN") (pintype "input"))
      (node (ref "IC4") (pin "GND") (pinfunction "GND_GND") (pintype "input"))
      (node (ref "J1") (pin "1") (pinfunction "1_1") (pintype "passive"))
      (node (ref "J1") (pin "10") (pinfunction "10_10") (pintype "passive"))
      (node (ref "J1") (pin "16") (pinfunction "16_16") (pintype "passive"))
      (node (ref "J1") (pin "5") (pinfunction "5_5") (pintype "passive"))
      (node (ref "J1") (pin "7") (pinfunction "7_7") (pintype "passive"))
      (node (ref "J1") (pin "8") (pinfunction "8_8") (pintype "passive"))
      (node (ref "J1") (pin "9") (pinfunction "9_9") (pintype "passive"))
      (node (ref "OK1") (pin "3") (pinfunction "EMIT_3") (pintype "passive"))
      (node (ref "OK3") (pin "3") (pinfunction "EMIT_3") (pintype "passive"))
      (node (ref "OK4") (pin "3") (pinfunction "EMIT_3") (pintype "passive"))
      (node (ref "OK5") (pin "3") (pinfunction "EMIT_3") (pintype "passive"))
      (node (ref "OK6") (pin "3") (pinfunction "EMIT_3") (pintype "passive"))
      (node (ref "OK7") (pin "3") (pinfunction "EMIT_3") (pintype "passive"))
      (node (ref "R13") (pin "1") (pinfunction "1_1") (pintype "passive"))
      (node (ref "R14") (pin "1") (pinfunction "1_1") (pintype "passive"))
      (node (ref "R24") (pin "1") (pinfunction "1_1") (pintype "passive"))
      (node (ref "R29") (pin "1") (pinfunction "1_1") (pintype "passive"))
      (node (ref "R34") (pin "1") (pinfunction "1_1") (pintype "passive"))
      (node (ref "R39") (pin "1") (pinfunction "1_1") (pintype "passive"))
      (node (ref "R5") (pin "2") (pinfunction "2_2") (pintype "passive"))
      (node (ref "SJR1") (pin "9") (pinfunction "GND_9") (pintype "bidirectional"))
      (node (ref "T1") (pin "E") (pinfunction "E_E") (pintype "passive"))
      (node (ref "T3") (pin "E") (pinfunction "E_E") (pintype "passive"))
      (node (ref "T4") (pin "E") (pinfunction "E_E") (pintype "passive"))
      (node (ref "T5") (pin "E") (pinfunction "E_E") (pintype "passive"))
      (node (ref "T6") (pin "E") (pinfunction "E_E") (pintype "passive"))
      (node (ref "U$1") (pin "5") (pinfunction "GND_5") (pintype "bidirectional"))
      (node (ref "U1") (pin "1") (pinfunction "GND_1") (pintype "bidirectional"))
      (node (ref "V1") (pin "13") (pinfunction "~{G}_13") (pintype "input"))
      (node (ref "V1") (pin "8") (pinfunction "-UB_8") (pintype "power_in"))
      (node (ref "X10") (pin "2") (pinfunction "KL_2") (pintype "passive"))
      (node (ref "X11") (pin "2") (pinfunction "KL_2") (pintype "passive"))
      (node (ref "X14") (pin "2") (pinfunction "KL_2") (pintype "passive"))
      (node (ref "X7") (pin "2") (pinfunction "KL_2") (pintype "passive"))
      (node (ref "X9") (pin "2") (pinfunction "KL_2") (pintype "passive"))
    )
    (net (code "35") (name "HEATER_FED_SIG") (class "Default")
      (node (ref "C9") (pin "+") (pinfunction "+_+") (pintype "passive"))
      (node (ref "IC1") (pin "36") (pinfunction "(ADC4)PA4_36") (pintype "bidirectional"))
      (node (ref "R15") (pin "1") (pinfunction "1_1") (pintype "passive"))
    )
    (net (code "36") (name "HEATER_T1") (class "Default")
      (node (ref "U$1") (pin "3") (pinfunction "IP-_3") (pintype "bidirectional"))
      (node (ref "U$1") (pin "4") (pinfunction "IP-_4") (pintype "bidirectional"))
      (node (ref "X8") (pin "2") (pinfunction "KL_2") (pintype "passive"))
    )
    (net (code "37") (name "HEATER_T2") (class "Default")
      (node (ref "U$1") (pin "1") (pinfunction "IP+_1") (pintype "bidirectional"))
      (node (ref "U$1") (pin "2") (pinfunction "IP+_2") (pintype "bidirectional"))
      (node (ref "X8") (pin "1") (pinfunction "KL_1") (pintype "passive"))
    )
    (net (code "38") (name "IO0") (class "Default")
      (node (ref "R6") (pin "1") (pinfunction "1_1") (pintype "passive"))
      (node (ref "SJR1") (pin "12") (pinfunction "GPIO0_12") (pintype "bidirectional"))
    )
    (net (code "39") (name "IO2") (class "Default")
      (node (ref "SJR1") (pin "11") (pinfunction "GPIO2_11") (pintype "bidirectional"))
    )
    (net (code "40") (name "L") (class "Default")
      (node (ref "D1") (pin "C") (pinfunction "C_C") (pintype "passive"))
      (node (ref "D13") (pin "C") (pinfunction "C_C") (pintype "passive"))
      (node (ref "D14") (pin "A") (pinfunction "A_A") (pintype "passive"))
      (node (ref "D25") (pin "C") (pinfunction "C_C") (pintype "passive"))
      (node (ref "D30") (pin "A") (pinfunction "A_A") (pintype "passive"))
      (node (ref "D34") (pin "C") (pinfunction "C_C") (pintype "passive"))
      (node (ref "D39") (pin "A") (pinfunction "A_A") (pintype "passive"))
      (node (ref "D43") (pin "C") (pinfunction "C_C") (pintype "passive"))
      (node (ref "D48") (pin "A") (pinfunction "A_A") (pintype "passive"))
      (node (ref "D6") (pin "A") (pinfunction "A_A") (pintype "passive"))
      (node (ref "R1") (pin "2") (pinfunction "2_2") (pintype "passive"))
      (node (ref "R20") (pin "2") (pinfunction "2_2") (pintype "passive"))
      (node (ref "R25") (pin "2") (pinfunction "2_2") (pintype "passive"))
      (node (ref "R30") (pin "2") (pinfunction "2_2") (pintype "passive"))
      (node (ref "R35") (pin "2") (pinfunction "2_2") (pintype "passive"))
      (node (ref "X1") (pin "2") (pinfunction "KL_2") (pintype "passive"))
    )
    (net (code "41") (name "LCD_CLK") (class "Default")
      (node (ref "IC1") (pin "25") (pinfunction "(TMS)PC3_25") (pintype "bidirectional"))
      (node (ref "V1") (pin "11") (pinfunction "SRCK_11") (pintype "input"))
    )
    (net (code "42") (name "LCD_D") (class "Default")
      (node (ref "IC1") (pin "20") (pinfunction "(ICP)PD6_20") (pintype "bidirectional"))
      (node (ref "V1") (pin "14") (pinfunction "SER_14") (pintype "input"))
    )
    (net (code "43") (name "LCD_L") (class "Default")
      (node (ref "IC1") (pin "17") (pinfunction "(INT1)PD3_17") (pintype "bidirectional"))
      (node (ref "V1") (pin "12") (pinfunction "RCK_12") (pintype "input"))
    )
    (net (code "44") (name "LED_PWM") (class "Default")
      (node (ref "IC1") (pin "18") (pinfunction "(OC1B)PD4_18") (pintype "bidirectional"))
      (node (ref "R10") (pin "2") (pinfunction "2_2") (pintype "passive"))
    )
    (net (code "45") (name "N") (class "Default")
      (node (ref "X1") (pin "1") (pinfunction "KL_1") (pintype "passive"))
      (node (ref "X2") (pin "2") (pinfunction "KL_2") (pintype "passive"))
      (node (ref "X3") (pin "2") (pinfunction "KL_2") (pintype "passive"))
      (node (ref "X4") (pin "2") (pinfunction "KL_2") (pintype "passive"))
      (node (ref "X5") (pin "2") (pinfunction "KL_2") (pintype "passive"))
      (node (ref "X6") (pin "2") (pinfunction "KL_2") (pintype "passive"))
    )
    (net (code "46") (name "NRST") (class "Default")
      (node (ref "R3") (pin "2") (pinfunction "2_2") (pintype "passive"))
      (node (ref "SJR1") (pin "1") (pinfunction "REST_1") (pintype "bidirectional"))
    )
    (net (code "47") (name "Net-(B3-Pad+)") (class "Default")
      (node (ref "B3") (pin "+") (pinfunction "+_+") (pintype "passive"))
      (node (ref "R18") (pin "2") (pinfunction "2_2") (pintype "passive"))
    )
    (net (code "48") (name "Net-(C2-Pad1)") (class "Default")
      (node (ref "C2") (pin "1") (pinfunction "1_1") (pintype "passive"))
      (node (ref "D7") (pin "A") (pinfunction "A_A") (pintype "passive"))
      (node (ref "D8") (pin "C") (pinfunction "C_C") (pintype "passive"))
    )
    (net (code "49") (name "Net-(C13-Pad1)") (class "Default")
      (node (ref "C13") (pin "1") (pinfunction "1_1") (pintype "passive"))
      (node (ref "D22") (pin "A") (pinfunction "A_A") (pintype "passive"))
      (node (ref "D23") (pin "C") (pinfunction "C_C") (pintype "passive"))
    )
    (net (code "50") (name "Net-(C15-Pad1)") (class "Default")
      (node (ref "C15") (pin "1") (pinfunction "1_1") (pintype "passive"))
      (node (ref "D31") (pin "A") (pinfunction "A_A") (pintype "passive"))
      (node (ref "D32") (pin "C") (pinfunction "C_C") (pintype "passive"))
    )
    (net (code "51") (name "Net-(C17-Pad1)") (class "Default")
      (node (ref "C17") (pin "1") (pinfunction "1_1") (pintype "passive"))
      (node (ref "D40") (pin "A") (pinfunction "A_A") (pintype "passive"))
      (node (ref "D41") (pin "C") (pinfunction "C_C") (pintype "passive"))
    )
    (net (code "52") (name "Net-(C19-Pad1)") (class "Default")
      (node (ref "C19") (pin "1") (pinfunction "1_1") (pintype "passive"))
      (node (ref "D49") (pin "A") (pinfunction "A_A") (pintype "passive"))
      (node (ref "D50") (pin "C") (pinfunction "C_C") (pintype "passive"))
    )
    (net (code "53") (name "Net-(D1-PadA)") (class "Default")
      (node (ref "D1") (pin "A") (pinfunction "A_A") (pintype "passive"))
      (node (ref "D2") (pin "C") (pinfunction "C_C") (pintype "passive"))
    )
    (net (code "54") (name "Net-(D2-PadA)") (class "Default")
      (node (ref "D2") (pin "A") (pinfunction "A_A") (pintype "passive"))
      (node (ref "D3") (pin "C") (pinfunction "C_C") (pintype "passive"))
    )
    (net (code "55") (name "Net-(D4-PadA)") (class "Default")
      (node (ref "D4") (pin "A") (pinfunction "A_A") (pintype "passive"))
      (node (ref "D5") (pin "C") (pinfunction "C_C") (pintype "passive"))
    )
    (net (code "56") (name "Net-(D5-PadA)") (class "Default")
      (node (ref "D5") (pin "A") (pinfunction "A_A") (pintype "passive"))
      (node (ref "D6") (pin "C") (pinfunction "C_C") (pintype "passive"))
    )
    (net (code "57") (name "Net-(D9-PadA)") (class "Default")
      (node (ref "D9") (pin "A") (pinfunction "A_A") (pintype "passive"))
      (node (ref "R12") (pin "1") (pinfunction "1_1") (pintype "passive"))
    )
    (net (code "58") (name "Net-(D10-C)") (class "Default")
      (node (ref "D10") (pin "K") (pinfunction "C_K") (pintype "passive"))
      (node (ref "K1") (pin "4") (pinfunction "K_4") (pintype "passive"))
      (node (ref "T1") (pin "C") (pinfunction "C_C") (pintype "passive"))
    )
    (net (code "59") (name "Net-(D10-PadA)") (class "Default")
      (node (ref "D10") (pin "A") (pinfunction "A_A") (pintype "passive"))
      (node (ref "R7") (pin "1") (pinfunction "1_1") (pintype "passive"))
    )
    (net (code "60") (name "Net-(D11-PadC)") (class "Default")
      (node (ref "D11") (pin "C") (pinfunction "C_C") (pintype "passive"))
      (node (ref "D12") (pin "A") (pinfunction "A_A") (pintype "passive"))
    )
    (net (code "61") (name "Net-(D12-PadC)") (class "Default")
      (node (ref "D12") (pin "C") (pinfunction "C_C") (pintype "passive"))
      (node (ref "D13") (pin "A") (pinfunction "A_A") (pintype "passive"))
    )
    (net (code "62") (name "Net-(D14-PadC)") (class "Default")
      (node (ref "D14") (pin "C") (pinfunction "C_C") (pintype "passive"))
      (node (ref "D15") (pin "A") (pinfunction "A_A") (pintype "passive"))
    )
    (net (code "63") (name "Net-(D15-PadC)") (class "Default")
      (node (ref "D15") (pin "C") (pinfunction "C_C") (pintype "passive"))
      (node (ref "D52") (pin "A") (pinfunction "A_A") (pintype "passive"))
    )
    (net (code "64") (name "Net-(D24-C)") (class "Default")
      (node (ref "D24") (pin "K") (pinfunction "C_K") (pintype "passive"))
      (node (ref "K2") (pin "4") (pinfunction "K_4") (pintype "passive"))
      (node (ref "T3") (pin "C") (pinfunction "C_C") (pintype "passive"))
    )
    (net (code "65") (name "Net-(D24-PadA)") (class "Default")
      (node (ref "D24") (pin "A") (pinfunction "A_A") (pintype "passive"))
      (node (ref "R22") (pin "1") (pinfunction "1_1") (pintype "passive"))
    )
    (net (code "66") (name "Net-(D25-PadA)") (class "Default")
      (node (ref "D25") (pin "A") (pinfunction "A_A") (pintype "passive"))
      (node (ref "D26") (pin "C") (pinfunction "C_C") (pintype "passive"))
    )
    (net (code "67") (name "Net-(D26-PadA)") (class "Default")
      (node (ref "D26") (pin "A") (pinfunction "A_A") (pintype "passive"))
      (node (ref "D27") (pin "C") (pinfunction "C_C") (pintype "passive"))
    )
    (net (code "68") (name "Net-(D28-PadA)") (class "Default")
      (node (ref "D28") (pin "A") (pinfunction "A_A") (pintype "passive"))
      (node (ref "D29") (pin "C") (pinfunction "C_C") (pintype "passive"))
    )
    (net (code "69") (name "Net-(D29-PadA)") (class "Default")
      (node (ref "D29") (pin "A") (pinfunction "A_A") (pintype "passive"))
      (node (ref "D30") (pin "C") (pinfunction "C_C") (pintype "passive"))
    )
    (net (code "70") (name "Net-(D33-C)") (class "Default")
      (node (ref "D33") (pin "K") (pinfunction "C_K") (pintype "passive"))
      (node (ref "K3") (pin "4") (pinfunction "K_4") (pintype "passive"))
      (node (ref "T4") (pin "C") (pinfunction "C_C") (pintype "passive"))
    )
    (net (code "71") (name "Net-(D33-PadA)") (class "Default")
      (node (ref "D33") (pin "A") (pinfunction "A_A") (pintype "passive"))
      (node (ref "R27") (pin "1") (pinfunction "1_1") (pintype "passive"))
    )
    (net (code "72") (name "Net-(D34-PadA)") (class "Default")
      (node (ref "D34") (pin "A") (pinfunction "A_A") (pintype "passive"))
      (node (ref "D35") (pin "C") (pinfunction "C_C") (pintype "passive"))
    )
    (net (code "73") (name "Net-(D35-PadA)") (class "Default")
      (node (ref "D35") (pin "A") (pinfunction "A_A") (pintype "passive"))
      (node (ref "D36") (pin "C") (pinfunction "C_C") (pintype "passive"))
    )
    (net (code "74") (name "Net-(D37-PadA)") (class "Default")
      (node (ref "D37") (pin "A") (pinfunction "A_A") (pintype "passive"))
      (node (ref "D38") (pin "C") (pinfunction "C_C") (pintype "passive"))
    )
    (net (code "75") (name "Net-(D38-PadA)") (class "Default")
      (node (ref "D38") (pin "A") (pinfunction "A_A") (pintype "passive"))
      (node (ref "D39") (pin "C") (pinfunction "C_C") (pintype "passive"))
    )
    (net (code "76") (name "Net-(D42-C)") (class "Default")
      (node (ref "D42") (pin "K") (pinfunction "C_K") (pintype "passive"))
      (node (ref "K4") (pin "4") (pinfunction "K_4") (pintype "passive"))
      (node (ref "T5") (pin "C") (pinfunction "C_C") (pintype "passive"))
    )
    (net (code "77") (name "Net-(D42-PadA)") (class "Default")
      (node (ref "D42") (pin "A") (pinfunction "A_A") (pintype "passive"))
      (node (ref "R32") (pin "1") (pinfunction "1_1") (pintype "passive"))
    )
    (net (code "78") (name "Net-(D43-PadA)") (class "Default")
      (node (ref "D43") (pin "A") (pinfunction "A_A") (pintype "passive"))
      (node (ref "D44") (pin "C") (pinfunction "C_C") (pintype "passive"))
    )
    (net (code "79") (name "Net-(D44-PadA)") (class "Default")
      (node (ref "D44") (pin "A") (pinfunction "A_A") (pintype "passive"))
      (node (ref "D45") (pin "C") (pinfunction "C_C") (pintype "passive"))
    )
    (net (code "80") (name "Net-(D46-PadA)") (class "Default")
      (node (ref "D46") (pin "A") (pinfunction "A_A") (pintype "passive"))
      (node (ref "D47") (pin "C") (pinfunction "C_C") (pintype "passive"))
    )
    (net (code "81") (name "Net-(D47-PadA)") (class "Default")
      (node (ref "D47") (pin "A") (pinfunction "A_A") (pintype "passive"))
      (node (ref "D48") (pin "C") (pinfunction "C_C") (pintype "passive"))
    )
    (net (code "82") (name "Net-(D51-C)") (class "Default")
      (node (ref "D51") (pin "K") (pinfunction "C_K") (pintype "passive"))
      (node (ref "K5") (pin "4") (pinfunction "K_4") (pintype "passive"))
      (node (ref "T6") (pin "C") (pinfunction "C_C") (pintype "passive"))
    )
    (net (code "83") (name "Net-(D51-PadA)") (class "Default")
      (node (ref "D51") (pin "A") (pinfunction "A_A") (pintype "passive"))
      (node (ref "R37") (pin "1") (pinfunction "1_1") (pintype "passive"))
    )
    (net (code "84") (name "Net-(D60-PadA)") (class "Default")
      (node (ref "D60") (pin "A") (pinfunction "A_A") (pintype "passive"))
      (node (ref "R42") (pin "1") (pinfunction "1_1") (pintype "passive"))
    )
    (net (code "85") (name "Net-(IC1-XTAL1)") (class "Default")
      (node (ref "C5") (pin "2") (pinfunction "2_2") (pintype "passive"))
      (node (ref "IC1") (pin "13") (pinfunction "XTAL1_13") (pintype "bidirectional"))
      (node (ref "Q1") (pin "1") (pinfunction "1_1") (pintype "passive"))
    )
    (net (code "86") (name "Net-(IC1-XTAL2)") (class "Default")
      (node (ref "C3") (pin "2") (pinfunction "2_2") (pintype "passive"))
      (node (ref "IC1") (pin "12") (pinfunction "XTAL2_12") (pintype "bidirectional"))
      (node (ref "Q1") (pin "2") (pinfunction "2_2") (pintype "passive"))
    )
    (net (code "87") (name "Net-(K1-DS2)") (class "Default")
      (node (ref "D3") (pin "A") (pinfunction "A_A") (pintype "passive"))
      (node (ref "D4") (pin "C") (pinfunction "C_C") (pintype "passive"))
      (node (ref "K1") (pin "2") (pinfunction "DS2_2") (pintype "passive"))
      (node (ref "OK1") (pin "2") (pinfunction "C_2") (pintype "passive"))
    )
    (net (code "88") (name "Net-(K2-DS2)") (class "Default")
      (node (ref "D11") (pin "A") (pinfunction "A_A") (pintype "passive"))
      (node (ref "D52") (pin "C") (pinfunction "C_C") (pintype "passive"))
      (node (ref "K2") (pin "2") (pinfunction "DS2_2") (pintype "passive"))
      (node (ref "OK3") (pin "2") (pinfunction "C_2") (pintype "passive"))
    )
    (net (code "89") (name "Net-(K3-DS2)") (class "Default")
      (node (ref "D27") (pin "A") (pinfunction "A_A") (pintype "passive"))
      (node (ref "D28") (pin "C") (pinfunction "C_C") (pintype "passive"))
      (node (ref "K3") (pin "2") (pinfunction "DS2_2") (pintype "passive"))
      (node (ref "OK4") (pin "2") (pinfunction "C_2") (pintype "passive"))
    )
    (net (code "90") (name "Net-(K4-DS2)") (class "Default")
      (node (ref "D36") (pin "A") (pinfunction "A_A") (pintype "passive"))
      (node (ref "D37") (pin "C") (pinfunction "C_C") (pintype "passive"))
      (node (ref "K4") (pin "2") (pinfunction "DS2_2") (pintype "passive"))
      (node (ref "OK5") (pin "2") (pinfunction "C_2") (pintype "passive"))
    )
    (net (code "91") (name "Net-(K5-DS2)") (class "Default")
      (node (ref "D45") (pin "A") (pinfunction "A_A") (pintype "passive"))
      (node (ref "D46") (pin "C") (pinfunction "C_C") (pintype "passive"))
      (node (ref "K5") (pin "2") (pinfunction "DS2_2") (pintype "passive"))
      (node (ref "OK6") (pin "2") (pinfunction "C_2") (pintype "passive"))
    )
    (net (code "92") (name "Net-(OK1-A)") (class "Default")
      (node (ref "OK1") (pin "1") (pinfunction "A_1") (pintype "passive"))
      (node (ref "R1") (pin "1") (pinfunction "1_1") (pintype "passive"))
    )
    (net (code "93") (name "Net-(OK1-COL)") (class "Default")
      (node (ref "C2") (pin "2") (pinfunction "2_2") (pintype "passive"))
      (node (ref "OK1") (pin "4") (pinfunction "COL_4") (pintype "passive"))
      (node (ref "R2") (pin "1") (pinfunction "1_1") (pintype "passive"))
    )
    (net (code "94") (name "Net-(OK3-A)") (class "Default")
      (node (ref "OK3") (pin "1") (pinfunction "A_1") (pintype "passive"))
      (node (ref "R20") (pin "1") (pinfunction "1_1") (pintype "passive"))
    )
    (net (code "95") (name "Net-(OK3-COL)") (class "Default")
      (node (ref "C13") (pin "2") (pinfunction "2_2") (pintype "passive"))
      (node (ref "OK3") (pin "4") (pinfunction "COL_4") (pintype "passive"))
      (node (ref "R21") (pin "1") (pinfunction "1_1") (pintype "passive"))
    )
    (net (code "96") (name "Net-(OK4-A)") (class "Default")
      (node (ref "OK4") (pin "1") (pinfunction "A_1") (pintype "passive"))
      (node (ref "R25") (pin "1") (pinfunction "1_1") (pintype "passive"))
    )
    (net (code "97") (name "Net-(OK4-COL)") (class "Default")
      (node (ref "C15") (pin "2") (pinfunction "2_2") (pintype "passive"))
      (node (ref "OK4") (pin "4") (pinfunction "COL_4") (pintype "passive"))
      (node (ref "R26") (pin "1") (pinfunction "1_1") (pintype "passive"))
    )
    (net (code "98") (name "Net-(OK5-A)") (class "Default")
      (node (ref "OK5") (pin "1") (pinfunction "A_1") (pintype "passive"))
      (node (ref "R30") (pin "1") (pinfunction "1_1") (pintype "passive"))
    )
    (net (code "99") (name "Net-(OK5-COL)") (class "Default")
      (node (ref "C17") (pin "2") (pinfunction "2_2") (pintype "passive"))
      (node (ref "OK5") (pin "4") (pinfunction "COL_4") (pintype "passive"))
      (node (ref "R31") (pin "1") (pinfunction "1_1") (pintype "passive"))
    )
    (net (code "100") (name "Net-(OK6-A)") (class "Default")
      (node (ref "OK6") (pin "1") (pinfunction "A_1") (pintype "passive"))
      (node (ref "R35") (pin "1") (pinfunction "1_1") (pintype "passive"))
    )
    (net (code "101") (name "Net-(OK6-COL)") (class "Default")
      (node (ref "C19") (pin "2") (pinfunction "2_2") (pintype "passive"))
      (node (ref "OK6") (pin "4") (pinfunction "COL_4") (pintype "passive"))
      (node (ref "R36") (pin "1") (pinfunction "1_1") (pintype "passive"))
    )
    (net (code "102") (name "Net-(OK7-A)") (class "Default")
      (node (ref "OK7") (pin "1") (pinfunction "A_1") (pintype "passive"))
      (node (ref "R18") (pin "1") (pinfunction "1_1") (pintype "passive"))
    )
    (net (code "103") (name "Net-(OK7-C)") (class "Default")
      (node (ref "B3") (pin "-") (pinfunction "-_-") (pintype "passive"))
      (node (ref "OK7") (pin "2") (pinfunction "C_2") (pintype "passive"))
    )
    (net (code "104") (name "Net-(R9-Pad2)") (class "Default")
      (node (ref "R9") (pin "2") (pinfunction "2_2") (pintype "passive"))
      (node (ref "T1") (pin "B") (pinfunction "B_B") (pintype "passive"))
    )
    (net (code "105") (name "Net-(R14-Pad2)") (class "Default")
      (node (ref "R14") (pin "2") (pinfunction "2_2") (pintype "passive"))
      (node (ref "SG1") (pin "-") (pinfunction "-_-") (pintype "passive"))
    )
    (net (code "106") (name "Net-(R23-Pad2)") (class "Default")
      (node (ref "R23") (pin "2") (pinfunction "2_2") (pintype "passive"))
      (node (ref "T3") (pin "B") (pinfunction "B_B") (pintype "passive"))
    )
    (net (code "107") (name "Net-(R28-Pad2)") (class "Default")
      (node (ref "R28") (pin "2") (pinfunction "2_2") (pintype "passive"))
      (node (ref "T4") (pin "B") (pinfunction "B_B") (pintype "passive"))
    )
    (net (code "108") (name "Net-(R33-Pad2)") (class "Default")
      (node (ref "R33") (pin "2") (pinfunction "2_2") (pintype "passive"))
      (node (ref "T5") (pin "B") (pinfunction "B_B") (pintype "passive"))
    )
    (net (code "109") (name "Net-(R38-Pad2)") (class "Default")
      (node (ref "R38") (pin "2") (pinfunction "2_2") (pintype "passive"))
      (node (ref "T6") (pin "B") (pinfunction "B_B") (pintype "passive"))
    )
    (net (code "110") (name "Net-(U$1-FILT)") (class "Default")
      (node (ref "C31") (pin "1") (pinfunction "1_1") (pintype "passive"))
      (node (ref "U$1") (pin "6") (pinfunction "FILT_6") (pintype "bidirectional"))
    )
    (net (code "111") (name "Net-(U$1-VOUT)") (class "Default")
      (node (ref "R15") (pin "2") (pinfunction "2_2") (pintype "passive"))
      (node (ref "U$1") (pin "7") (pinfunction "VOUT_7") (pintype "bidirectional"))
    )
    (net (code "112") (name "OK") (class "Default")
      (node (ref "IC1") (pin "39") (pinfunction "(ADC1)PA1_39") (pintype "bidirectional"))
      (node (ref "X13") (pin "2") (pinfunction "KL_2") (pintype "passive"))
    )
    (net (code "113") (name "OUT_PUMP") (class "Default")
      (node (ref "K5") (pin "1") (pinfunction "DS1_1") (pintype "passive"))
      (node (ref "X6") (pin "1") (pinfunction "KL_1") (pintype "passive"))
    )
    (net (code "114") (name "OUT_S1_GAS") (class "Default")
      (node (ref "K4") (pin "1") (pinfunction "DS1_1") (pintype "passive"))
      (node (ref "X2") (pin "1") (pinfunction "KL_1") (pintype "passive"))
    )
    (net (code "115") (name "OUT_S2_WAT") (class "Default")
      (node (ref "K3") (pin "1") (pinfunction "DS1_1") (pintype "passive"))
      (node (ref "X3") (pin "1") (pinfunction "KL_1") (pintype "passive"))
    )
    (net (code "116") (name "OUT_S3_VAP") (class "Default")
      (node (ref "K2") (pin "1") (pinfunction "DS1_1") (pintype "passive"))
      (node (ref "X4") (pin "1") (pinfunction "KL_1") (pintype "passive"))
    )
    (net (code "117") (name "OUT_S4_DRY") (class "Default")
      (node (ref "K1") (pin "1") (pinfunction "DS1_1") (pintype "passive"))
      (node (ref "X5") (pin "1") (pinfunction "KL_1") (pintype "passive"))
    )
    (net (code "118") (name "PRES_SEN") (class "Default")
      (node (ref "IC1") (pin "6") (pinfunction "(MOSI)PB5_6") (pintype "bidirectional"))
      (node (ref "X10") (pin "1") (pinfunction "KL_1") (pintype "passive"))
    )
    (net (code "119") (name "PUMP_FED_SIG") (class "Default")
      (node (ref "C33") (pin "1") (pinfunction "1_1") (pintype "passive"))
      (node (ref "D22") (pin "C") (pinfunction "C_C") (pintype "passive"))
      (node (ref "IC1") (pin "23") (pinfunction "(SDA)PC1_23") (pintype "bidirectional"))
      (node (ref "R24") (pin "2") (pinfunction "2_2") (pintype "passive"))
    )
    (net (code "120") (name "REST") (class "Default")
      (node (ref "IC1") (pin "9") (pinfunction "RESET_9") (pintype "input"))
      (node (ref "JP1") (pin "2") (pinfunction "2_2") (pintype "passive"))
      (node (ref "R8") (pin "1") (pinfunction "1_1") (pintype "passive"))
    )
    (net (code "121") (name "REST_OUT") (class "Default")
      (node (ref "JP1") (pin "1") (pinfunction "1_1") (pintype "passive"))
      (node (ref "SJR1") (pin "13") (pinfunction "GPIO4_13") (pintype "bidirectional"))
    )
    (net (code "122") (name "RS") (class "Default")
      (node (ref "J1") (pin "4") (pinfunction "4_4") (pintype "passive"))
      (node (ref "V1") (pin "7") (pinfunction "QH_7") (pintype "tri_state"))
    )
    (net (code "123") (name "S1_GAS_FED_SIG") (class "Default")
      (node (ref "C35") (pin "1") (pinfunction "1_1") (pintype "passive"))
      (node (ref "D40") (pin "C") (pinfunction "C_C") (pintype "passive"))
      (node (ref "IC1") (pin "35") (pinfunction "(ADC5)PA5_35") (pintype "bidirectional"))
      (node (ref "R34") (pin "2") (pinfunction "2_2") (pintype "passive"))
    )
    (net (code "124") (name "S2_WAT_FED_SIG") (class "Default")
      (node (ref "C34") (pin "1") (pinfunction "1_1") (pintype "passive"))
      (node (ref "D31") (pin "C") (pinfunction "C_C") (pintype "passive"))
      (node (ref "IC1") (pin "27") (pinfunction "(TDI)PC5_27") (pintype "bidirectional"))
      (node (ref "R29") (pin "2") (pinfunction "2_2") (pintype "passive"))
    )
    (net (code "125") (name "S3_VAP_FED_SIG") (class "Default")
      (node (ref "C36") (pin "1") (pinfunction "1_1") (pintype "passive"))
      (node (ref "D49") (pin "C") (pinfunction "C_C") (pintype "passive"))
      (node (ref "IC1") (pin "29") (pinfunction "(TOSC2)PC7_29") (pintype "bidirectional"))
      (node (ref "R39") (pin "2") (pinfunction "2_2") (pintype "passive"))
    )
    (net (code "126") (name "S4_DRY_FED_SIG") (class "Default")
      (node (ref "C32") (pin "1") (pinfunction "1_1") (pintype "passive"))
      (node (ref "D7") (pin "C") (pinfunction "C_C") (pintype "passive"))
      (node (ref "IC1") (pin "21") (pinfunction "(OC2)PD7_21") (pintype "bidirectional"))
      (node (ref "R13") (pin "2") (pinfunction "2_2") (pintype "passive"))
    )
    (net (code "127") (name "SCL3") (class "Default")
      (node (ref "SJR1") (pin "14") (pinfunction "GPIO5_14") (pintype "bidirectional"))
    )
    (net (code "128") (name "TCK+") (class "Default")
      (node (ref "U1") (pin "3") (pinfunction "T+_3") (pintype "bidirectional"))
      (node (ref "X15") (pin "2") (pinfunction "KL_2") (pintype "passive"))
    )
    (net (code "129") (name "TCK-") (class "Default")
      (node (ref "U1") (pin "2") (pinfunction "T-_2") (pintype "bidirectional"))
      (node (ref "X15") (pin "1") (pinfunction "KL_1") (pintype "passive"))
    )
    (net (code "130") (name "T_CLK") (class "Default")
      (node (ref "IC1") (pin "3") (pinfunction "(AIN0/INT2)PB2_3") (pintype "bidirectional"))
      (node (ref "U1") (pin "6") (pinfunction "~{CS}_6") (pintype "bidirectional"))
    )
    (net (code "131") (name "T_CS") (class "Default")
      (node (ref "IC1") (pin "2") (pinfunction "(T1)PB1_2") (pintype "bidirectional"))
      (node (ref "U1") (pin "5") (pinfunction "SCK_5") (pintype "bidirectional"))
    )
    (net (code "132") (name "T_DO") (class "Default")
      (node (ref "IC1") (pin "4") (pinfunction "(AIN1/OC0)PB3_4") (pintype "bidirectional"))
      (node (ref "U1") (pin "7") (pinfunction "(MI)SO_7") (pintype "bidirectional"))
    )
    (net (code "133") (name "UP") (class "Default")
      (node (ref "IC1") (pin "38") (pinfunction "(ADC2)PA2_38") (pintype "bidirectional"))
      (node (ref "X13") (pin "1") (pinfunction "KL_1") (pintype "passive"))
    )
    (net (code "134") (name "VEE") (class "Default")
      (node (ref "C11") (pin "2") (pinfunction "2_2") (pintype "passive"))
      (node (ref "C4") (pin "+") (pinfunction "+_+") (pintype "passive"))
      (node (ref "J1") (pin "3") (pinfunction "3_3") (pintype "passive"))
      (node (ref "R11") (pin "1") (pinfunction "1_1") (pintype "passive"))
    )
    (net (code "135") (name "VIN") (class "Default")
      (node (ref "B2") (pin "+") (pinfunction "+_+") (pintype "passive"))
      (node (ref "C22") (pin "+") (pinfunction "+_+") (pintype "passive"))
      (node (ref "C23") (pin "2") (pinfunction "2_2") (pintype "passive"))
      (node (ref "IC2") (pin "IN") (pinfunction "IN_IN") (pintype "input"))
      (node (ref "IC4") (pin "IN") (pinfunction "IN_IN") (pintype "input"))
      (node (ref "R42") (pin "2") (pinfunction "2_2") (pintype "passive"))
    )
    (net (code "136") (name "WATER_SEN") (class "Default")
      (node (ref "IC1") (pin "34") (pinfunction "(ADC6)PA6_34") (pintype "bidirectional"))
      (node (ref "R16") (pin "1") (pinfunction "1_1") (pintype "passive"))
      (node (ref "X9") (pin "1") (pinfunction "KL_1") (pintype "passive"))
    )
    (net (code "137") (name "ZERO_CROSS") (class "Default")
      (node (ref "IC1") (pin "16") (pinfunction "(INT0)PD2_16") (pintype "bidirectional"))
      (node (ref "OK7") (pin "4") (pinfunction "COL_4") (pintype "passive"))
      (node (ref "R19") (pin "2") (pinfunction "2_2") (pintype "passive"))
    )
    (net (code "138") (name "unconnected-(IC1-(SS)PB4-Pad5)") (class "Default")
      (node (ref "IC1") (pin "5") (pinfunction "(SS)PB4_5") (pintype "bidirectional"))
    )
    (net (code "139") (name "unconnected-(IC1-AREF-Pad32)") (class "Default")
      (node (ref "IC1") (pin "32") (pinfunction "AREF_32") (pintype "passive"))
    )
    (net (code "140") (name "unconnected-(SJR1-CS0-Pad17)") (class "Default")
      (node (ref "SJR1") (pin "17") (pinfunction "CS0_17") (pintype "bidirectional"))
    )
    (net (code "141") (name "unconnected-(SJR1-GPIO9-Pad19)") (class "Default")
      (node (ref "SJR1") (pin "19") (pinfunction "GPIO9_19") (pintype "bidirectional"))
    )
    (net (code "142") (name "unconnected-(SJR1-GPIO10-Pad20)") (class "Default")
      (node (ref "SJR1") (pin "20") (pinfunction "GPIO10_20") (pintype "bidirectional"))
    )
    (net (code "143") (name "unconnected-(SJR1-MISO-Pad18)") (class "Default")
      (node (ref "SJR1") (pin "18") (pinfunction "MISO_18") (pintype "bidirectional"))
    )
    (net (code "144") (name "unconnected-(SJR1-MOSI-Pad21)") (class "Default")
      (node (ref "SJR1") (pin "21") (pinfunction "MOSI_21") (pintype "bidirectional"))
    )
    (net (code "145") (name "unconnected-(SJR1-SCLK-Pad22)") (class "Default")
      (node (ref "SJR1") (pin "22") (pinfunction "SCLK_22") (pintype "bidirectional"))
    )
    (net (code "146") (name "unconnected-(V1C-QE-Pad4)") (class "Default")
      (node (ref "V1") (pin "4") (pinfunction "QE_4") (pintype "tri_state"))
    )
    (net (code "147") (name "unconnected-(V1C-QF-Pad5)") (class "Default")
      (node (ref "V1") (pin "5") (pinfunction "QF_5") (pintype "tri_state"))
    )
    (net (code "148") (name "unconnected-(V1C-QH*-Pad9)") (class "Default")
      (node (ref "V1") (pin "9") (pinfunction "QH*_9") (pintype "output"))
    )
  )
)
